# Sherline_Configuration.net
KiCad netlist of a schematic drawn in EAGLE
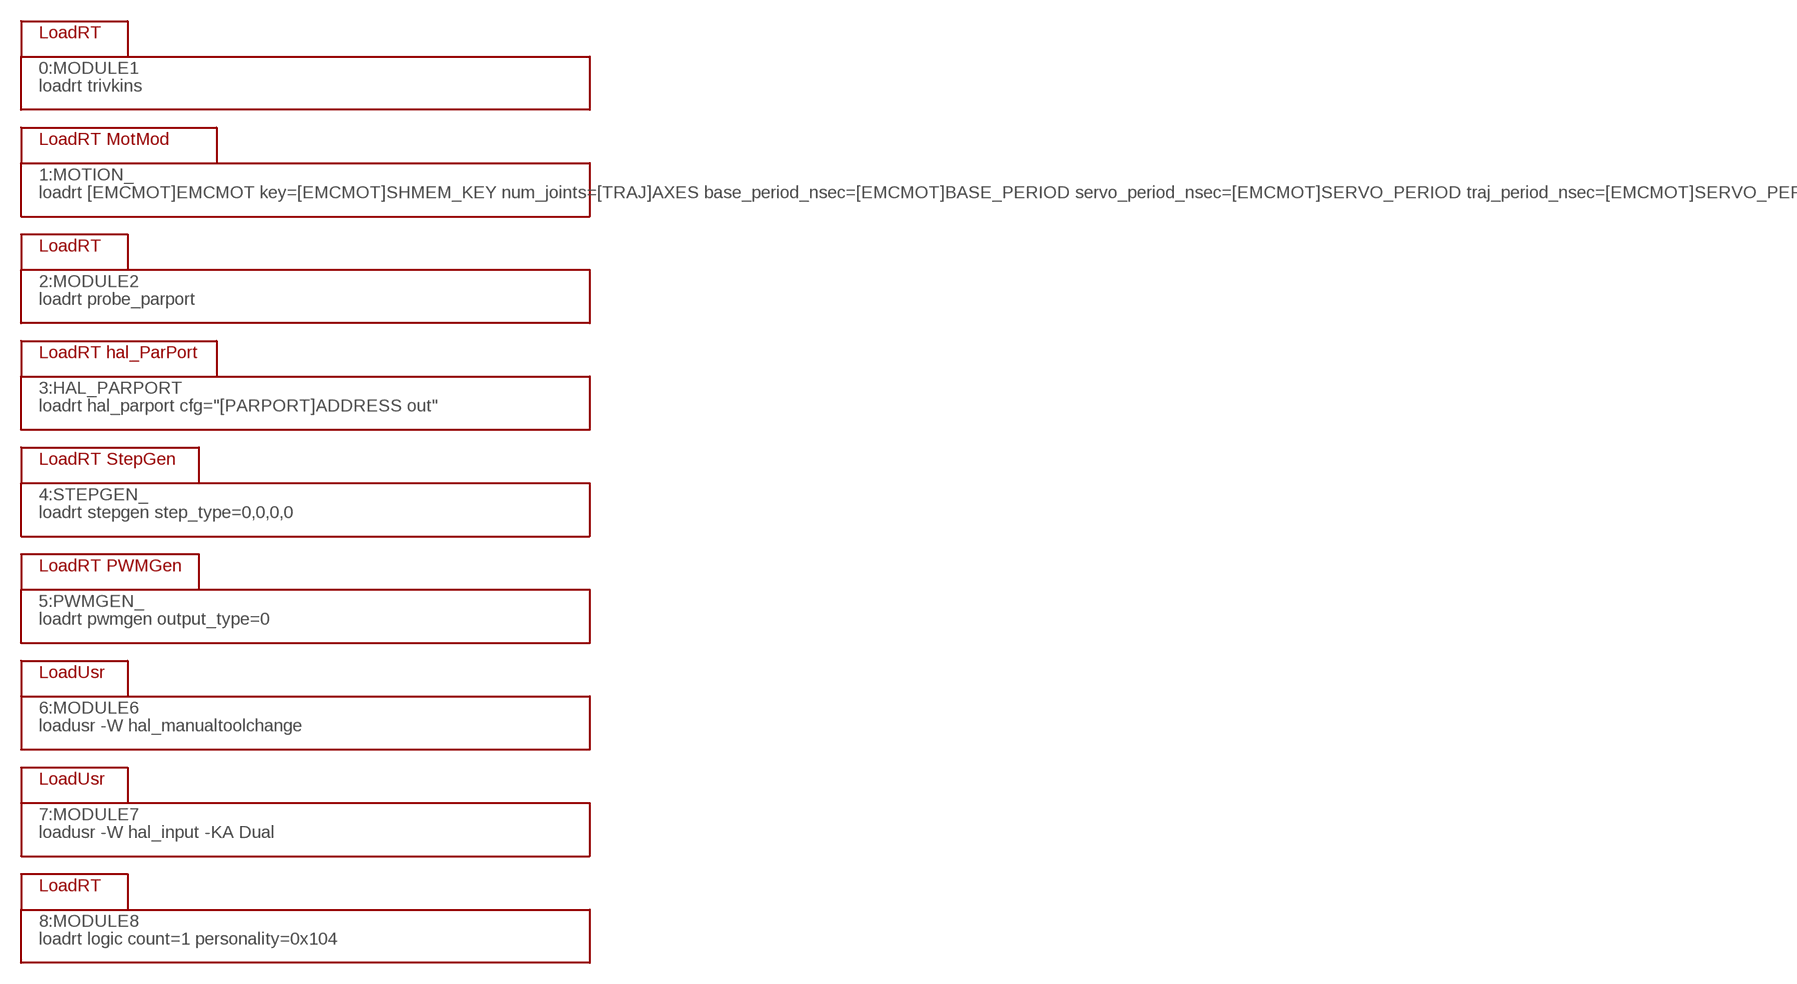
[diagram p0: schematic, sheet 1]
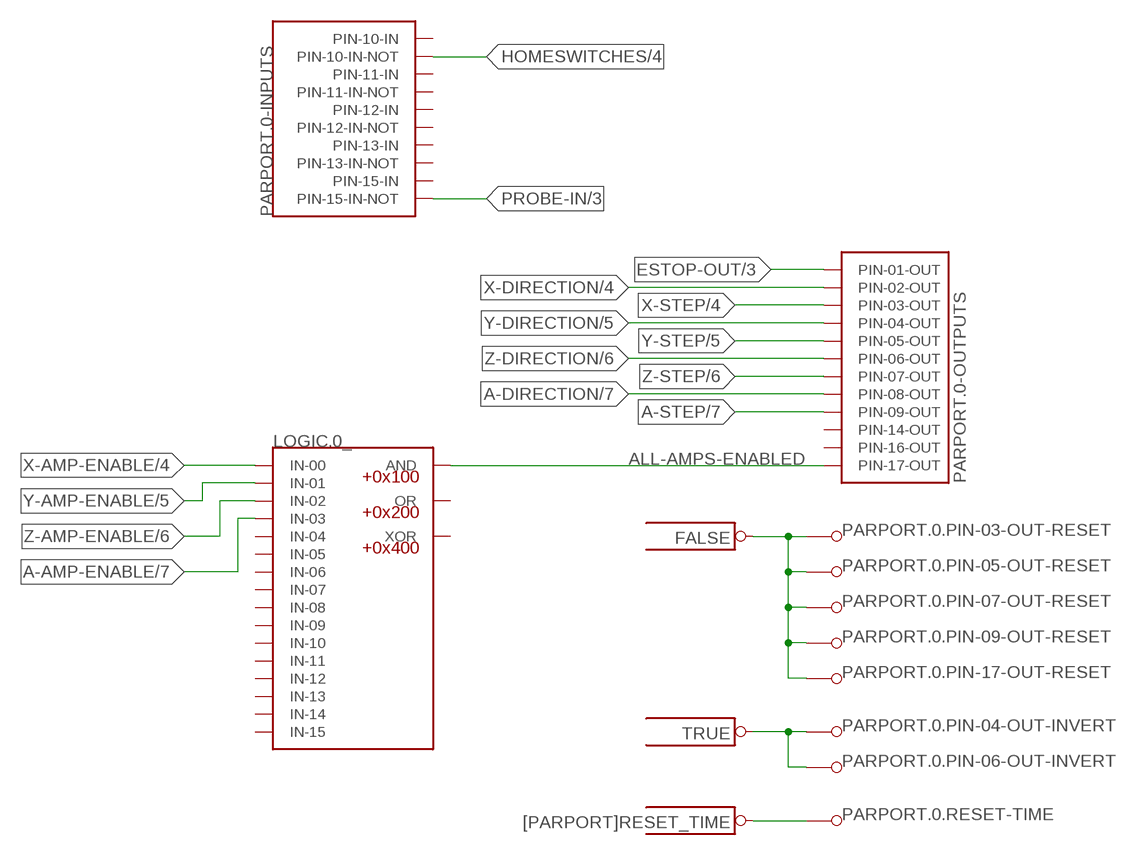
[diagram p1: schematic, sheet 2]
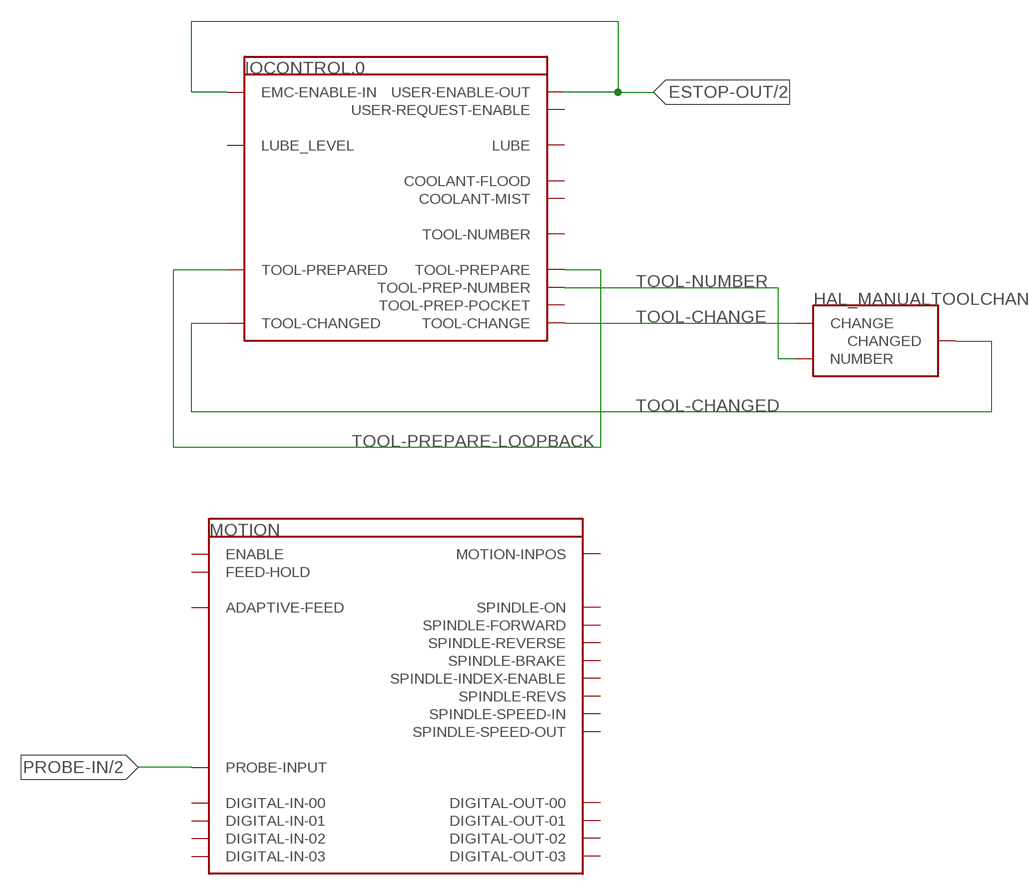
[diagram p2: schematic, sheet 3]
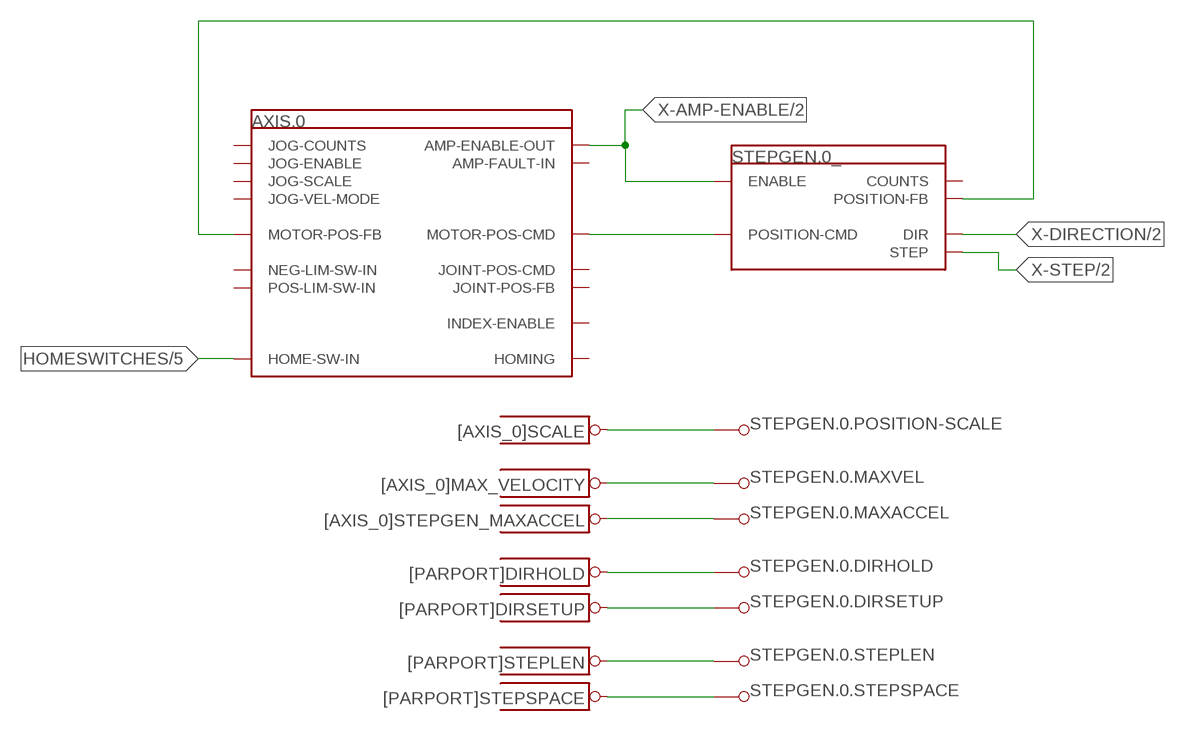
[diagram p3: schematic, sheet 4]
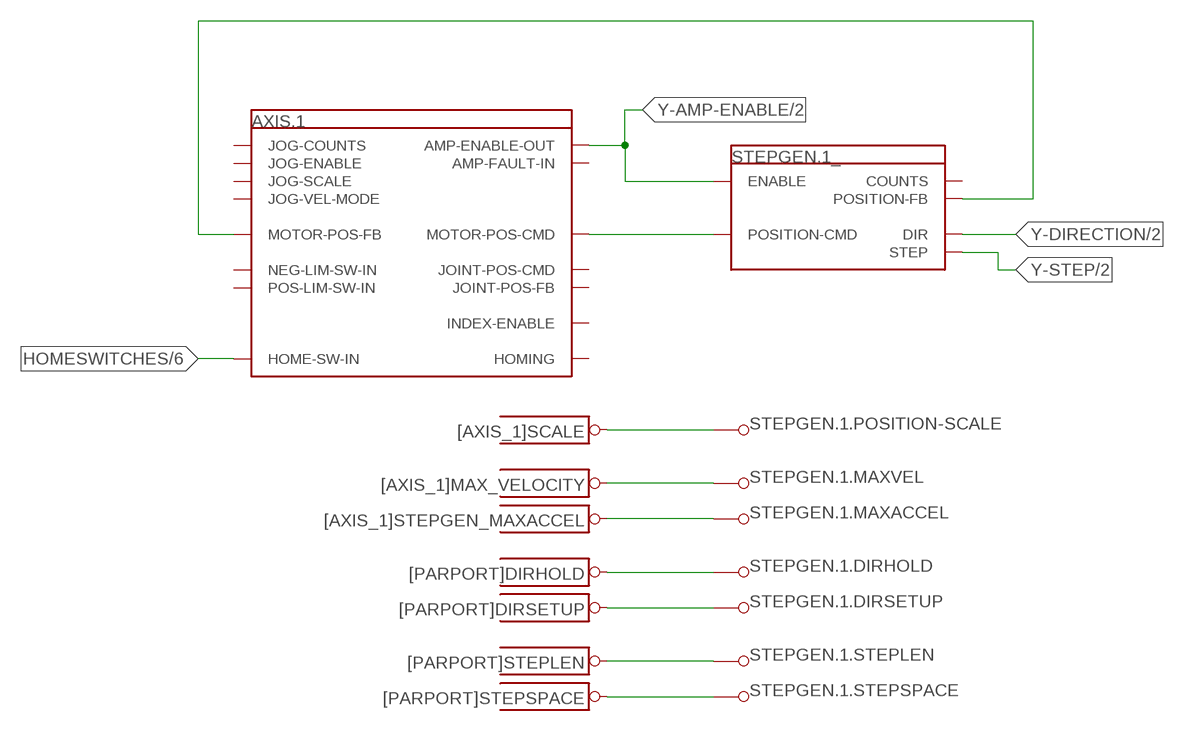
[diagram p4: schematic, sheet 5]
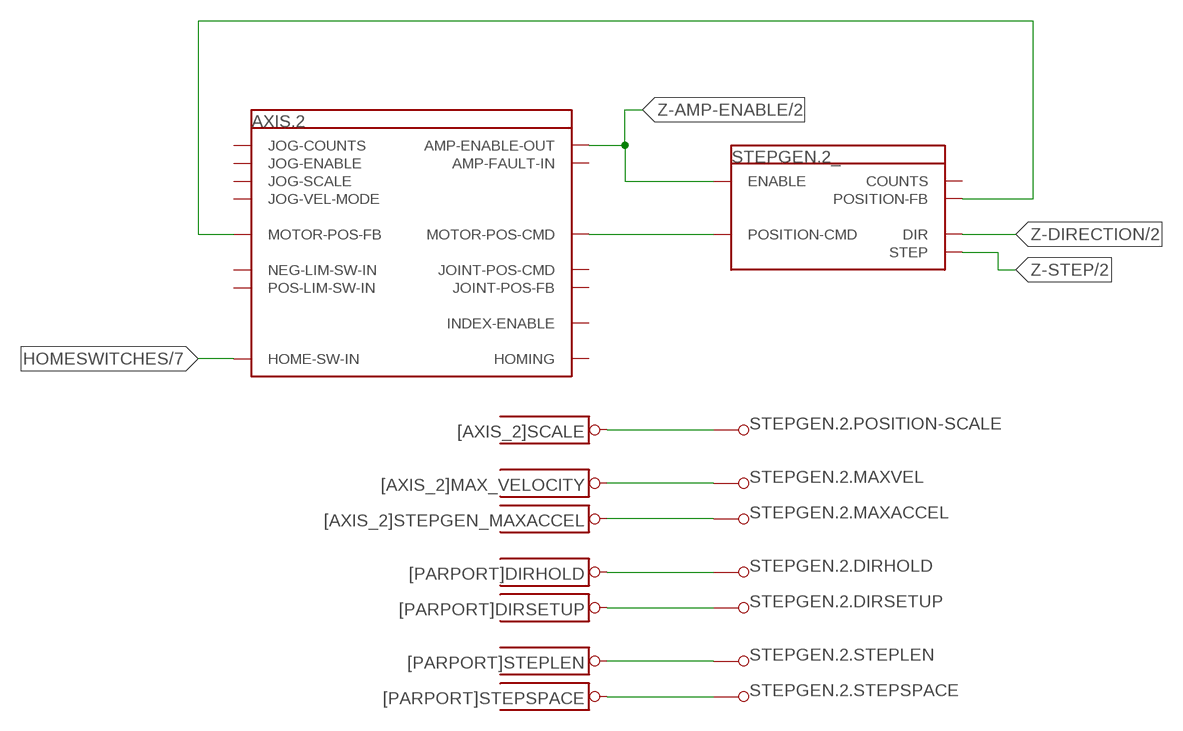
[diagram p5: schematic, sheet 6]
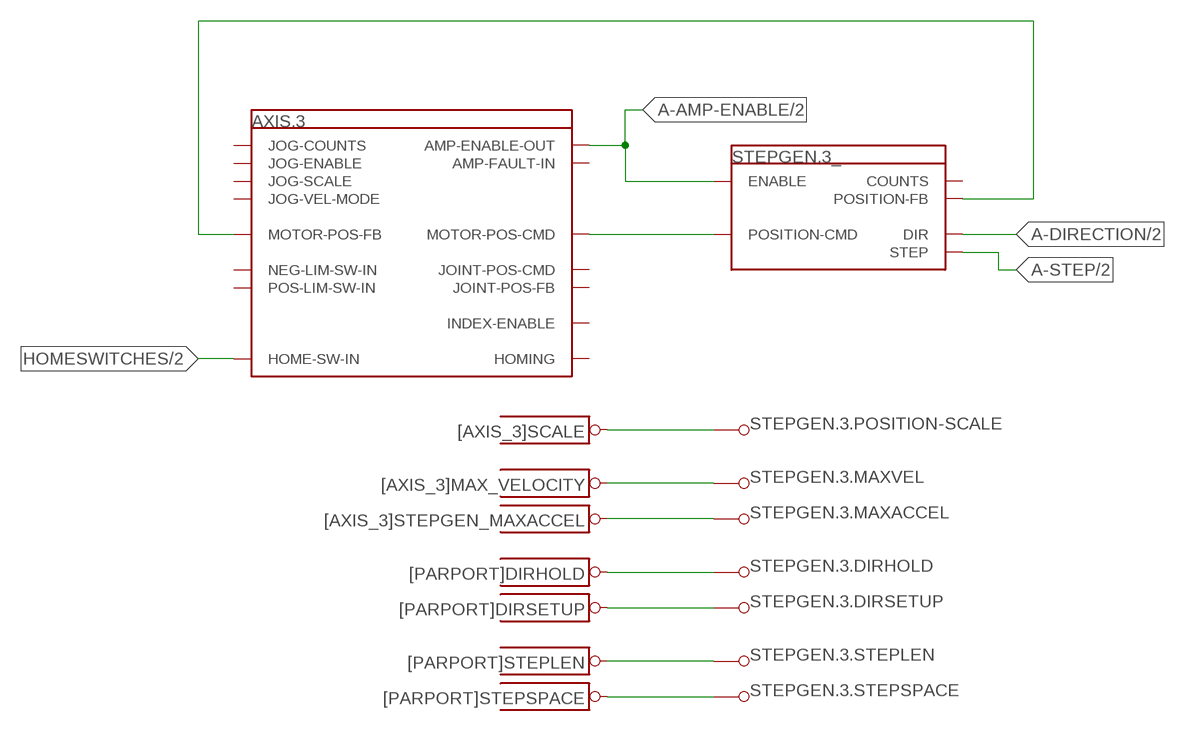
[diagram p6: schematic, sheet 7]
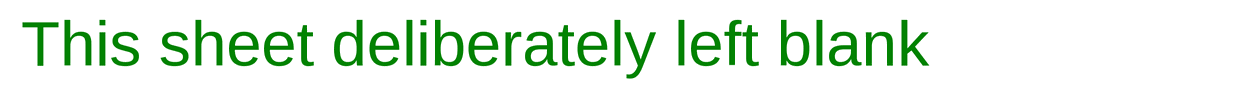
[diagram p7: schematic, sheet 8]
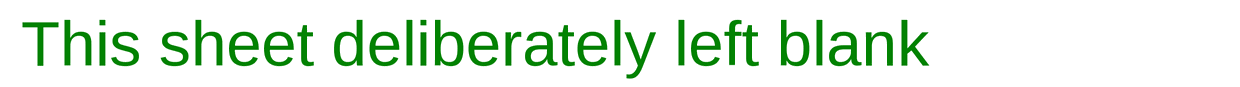
[diagram p8: schematic, sheet 9]
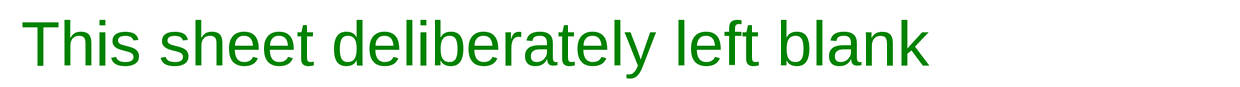
[diagram p9: schematic, sheet 10]
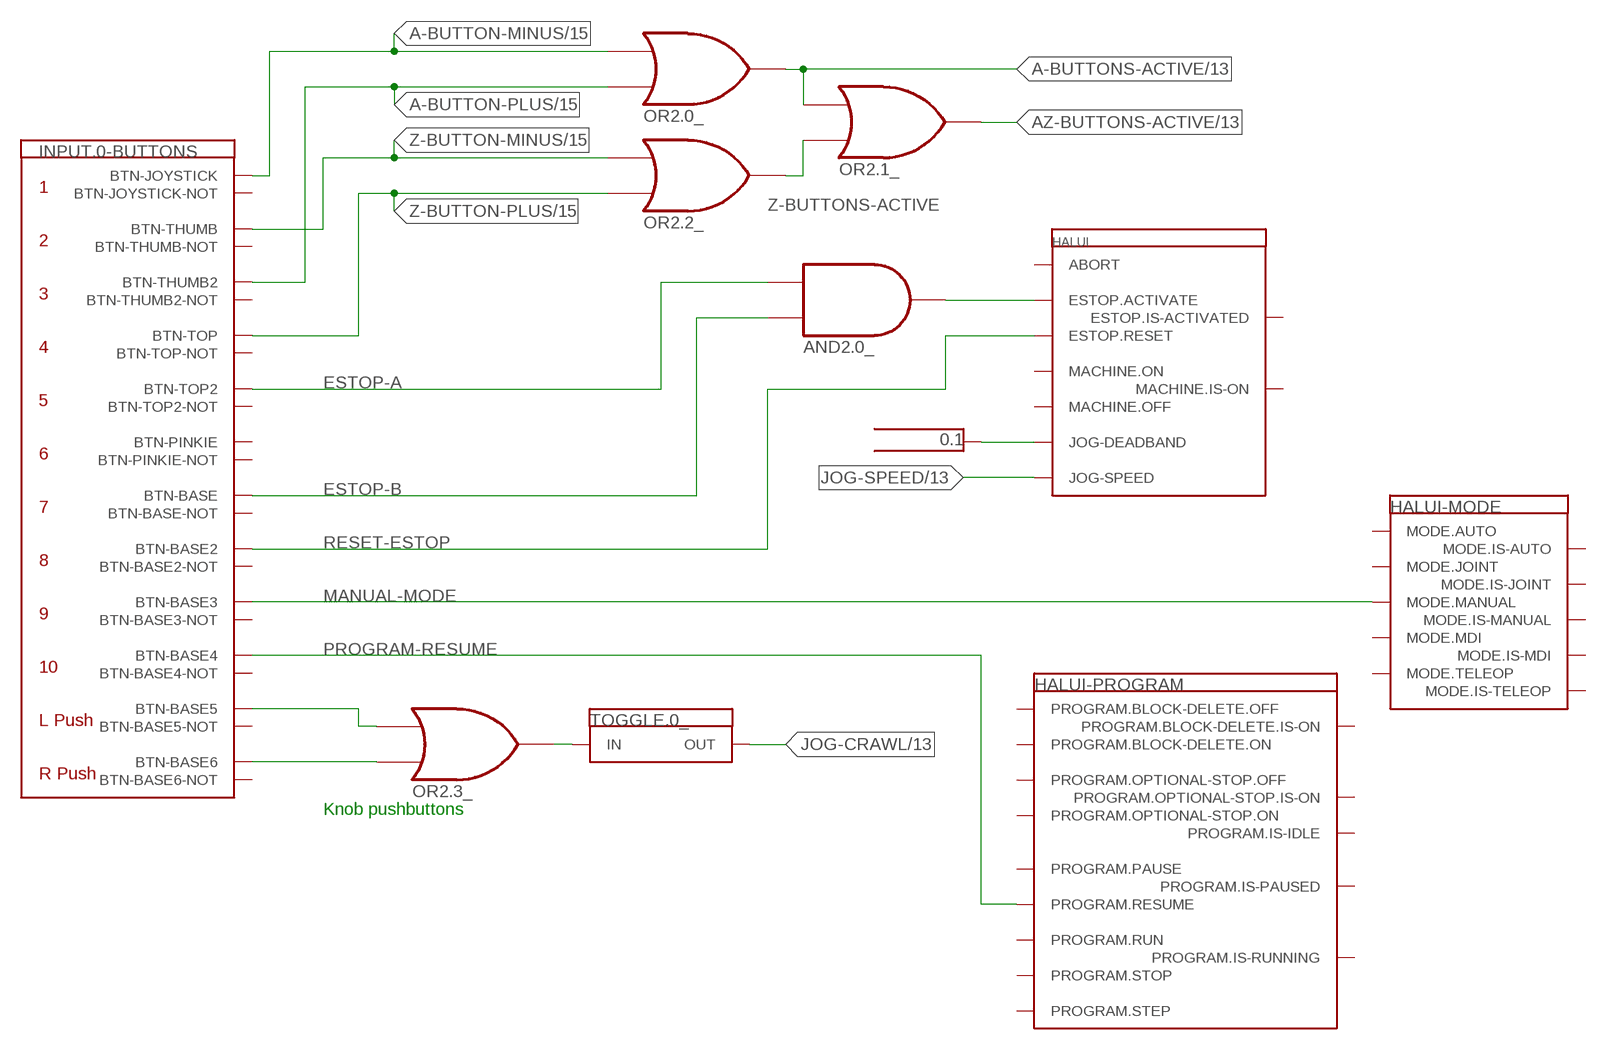
[diagram p10: schematic, sheet 11]
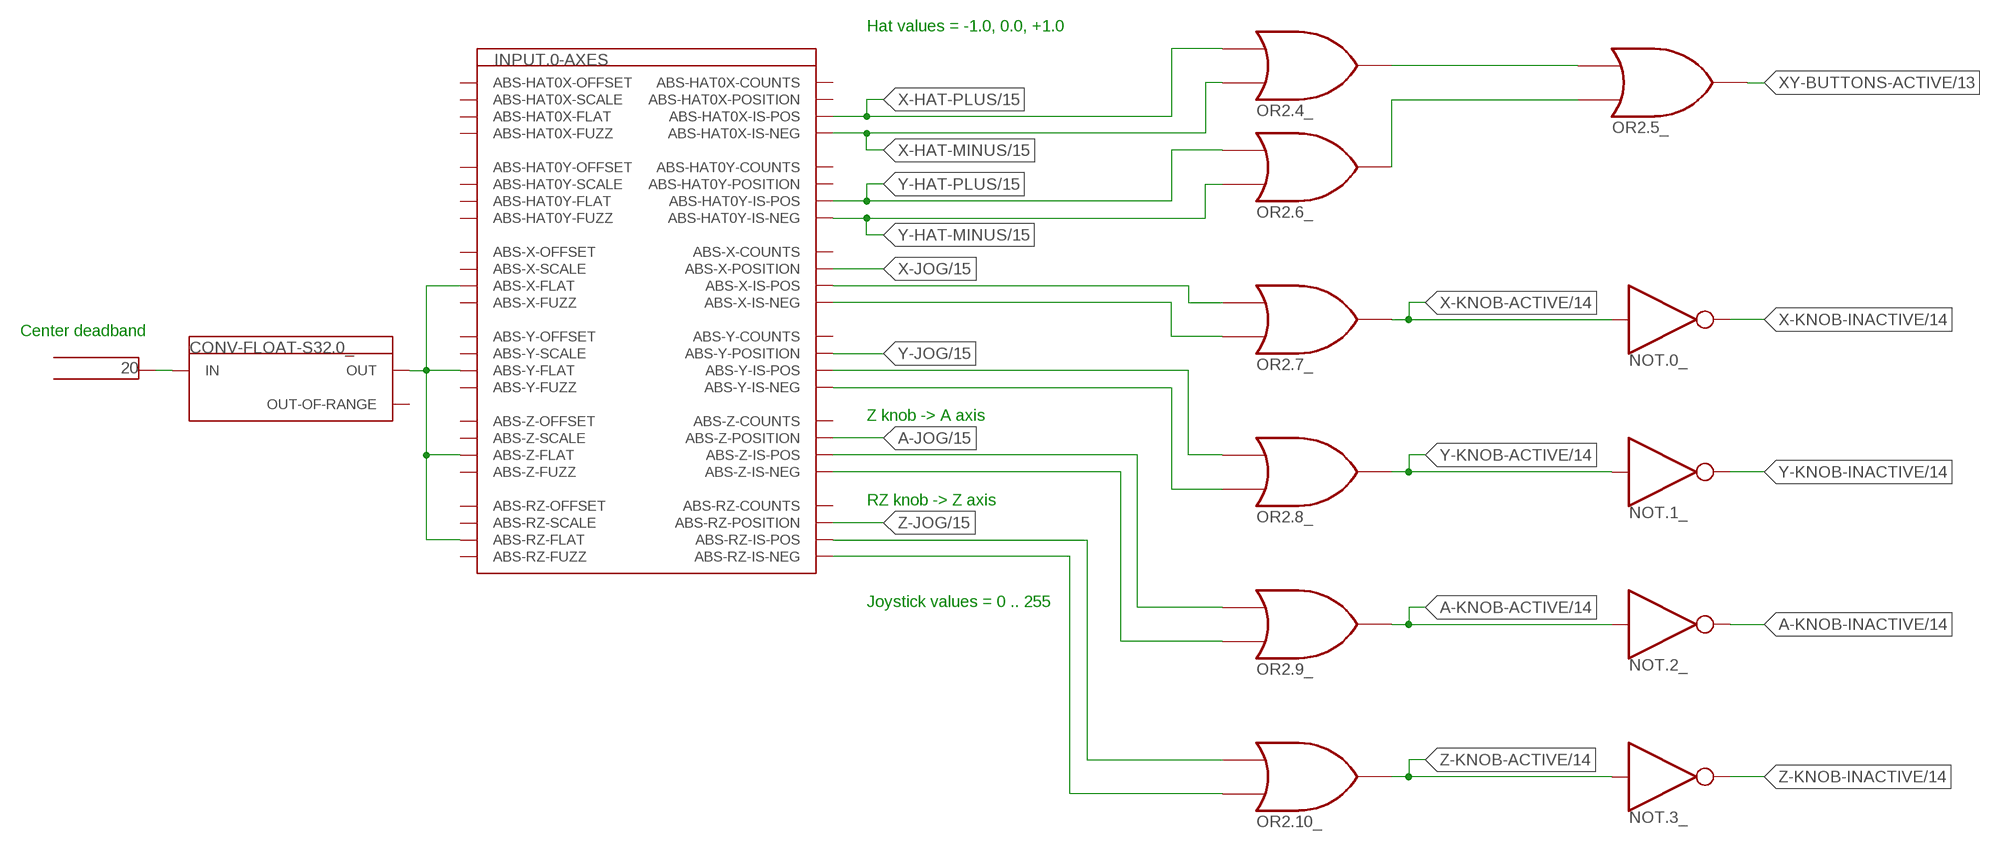
[diagram p11: schematic, sheet 12]
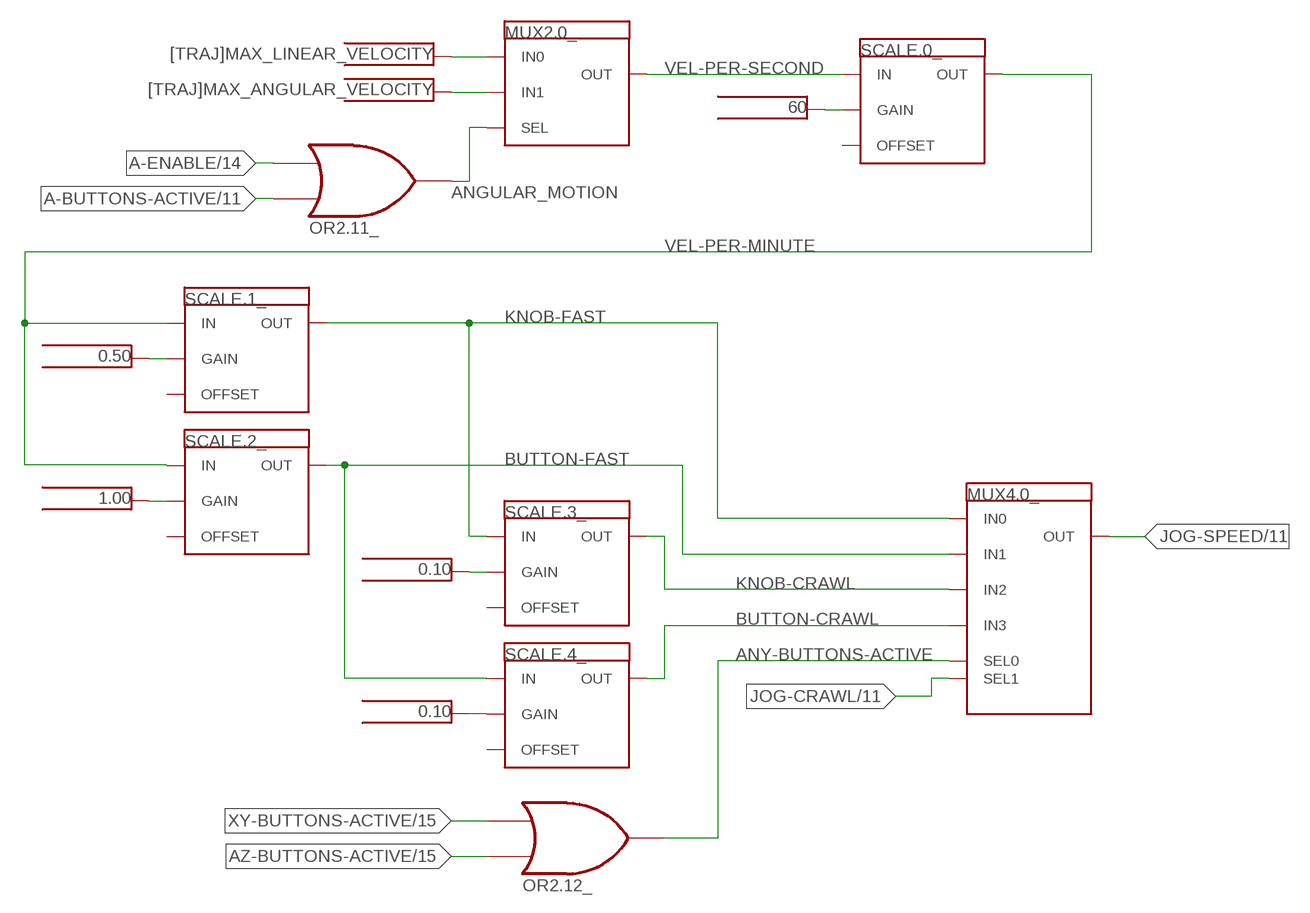
[diagram p12: schematic, sheet 13]
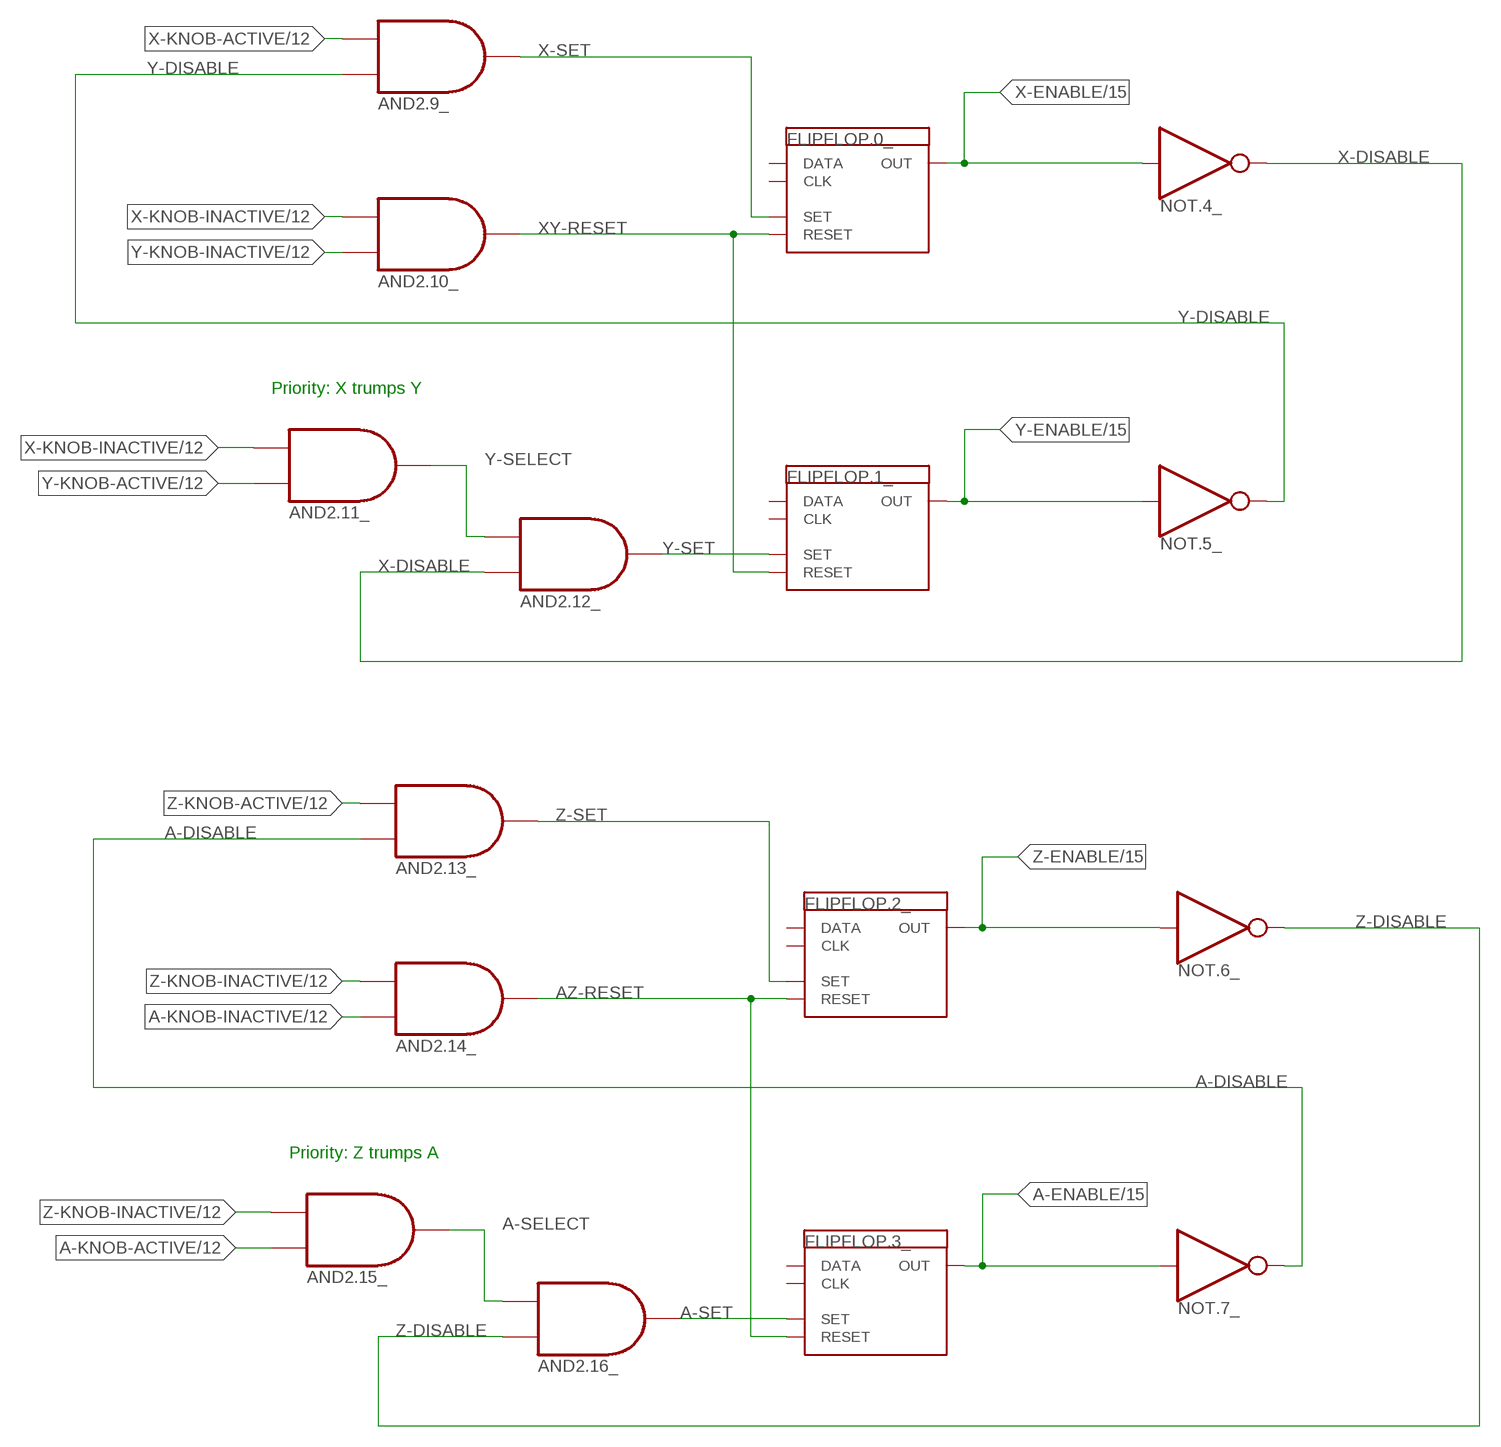
[diagram p13: schematic, sheet 14]
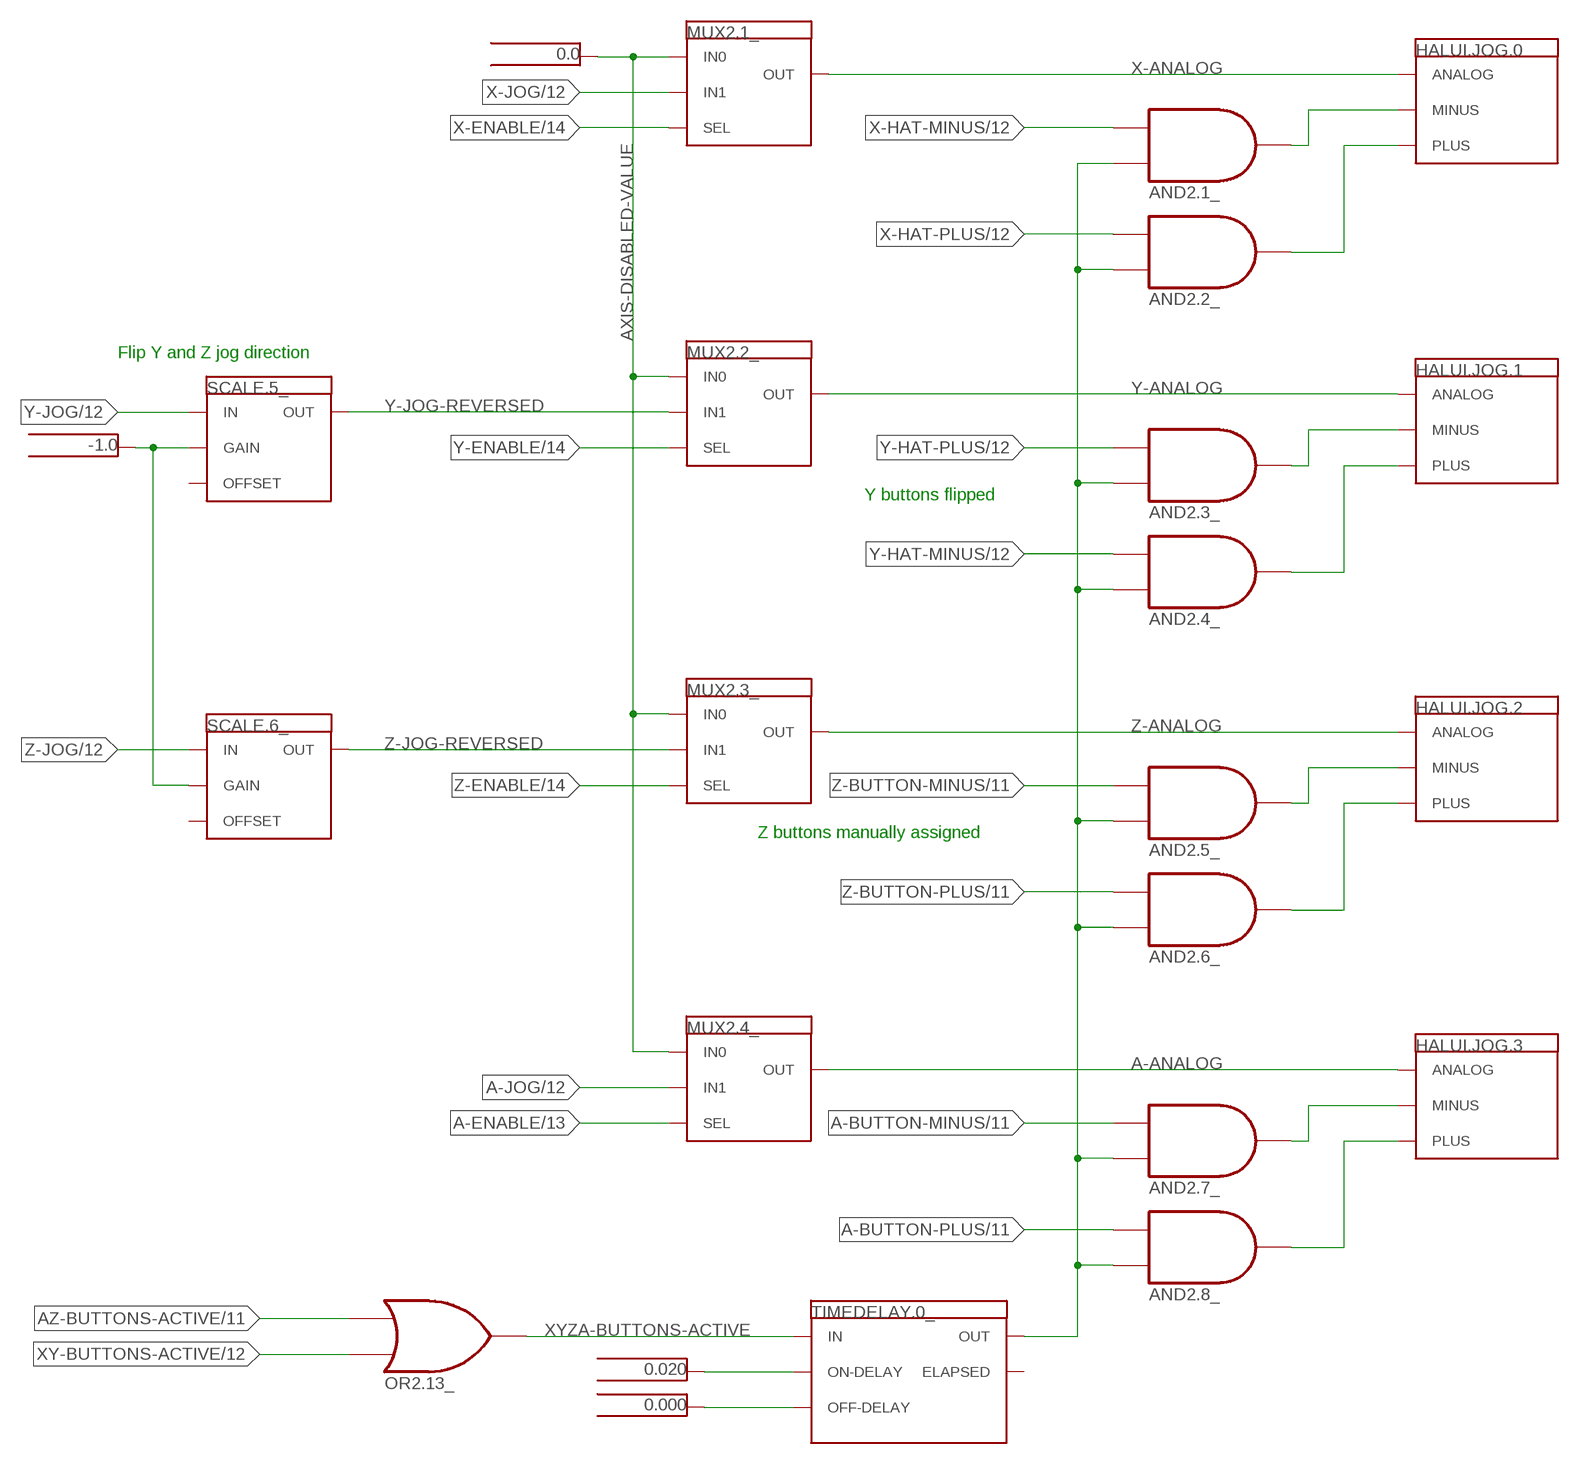
[diagram p14: schematic, sheet 15]
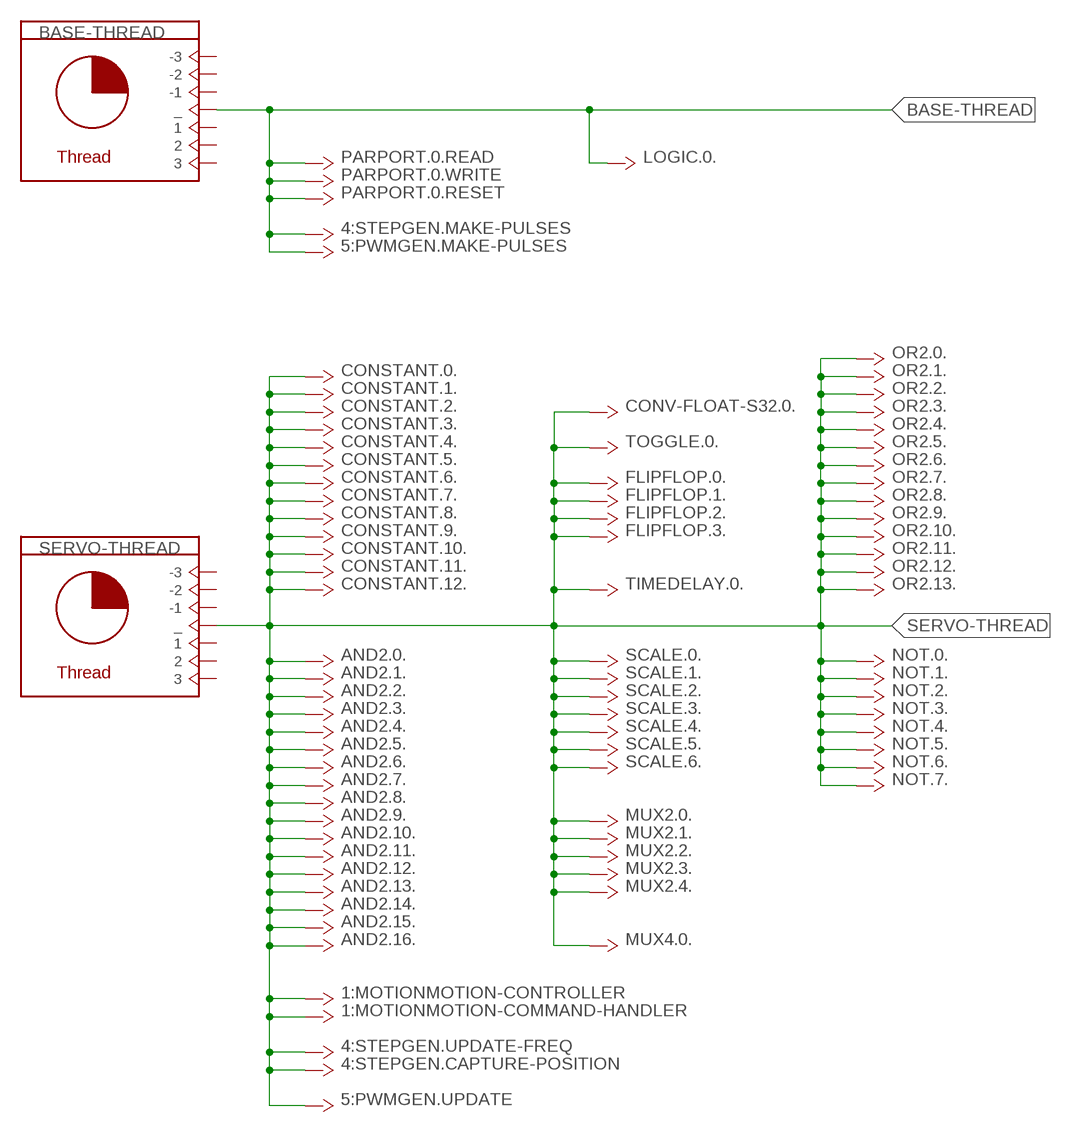
[diagram p15: schematic, sheet 16]

(export (version "E")
  (design (tool "Eeschema 10.0.6"))
  (components
    (comp (ref "1:MOTION")
      (value "loadrt [EMCMOT]EMCMOT key=[EMCMOT]SHMEM_KEY num_joints=[TRAJ]AXES base_period_nsec=[EMCMOT]BASE_PERIOD servo_period_nsec=[EMCMOT]SERVO_PERIOD traj_period_nsec=[EMCMOT]SERVO_PERIOD")
      (footprint "eagle-import:DUMMY")
      (libsource (lib "eagle-import") (part "LOADRT_MOTMOD"))
    )
    (comp (ref "4:STEPGEN")
      (value "loadrt stepgen step_type=0,0,0,0")
      (footprint "eagle-import:DUMMY")
      (libsource (lib "eagle-import") (part "LOADRT_STEPGEN"))
    )
    (comp (ref "5:PWMGEN")
      (value "loadrt pwmgen output_type=0")
      (footprint "eagle-import:DUMMY")
      (libsource (lib "eagle-import") (part "LOADRT_PWMGEN"))
    )
    (comp (ref "AND2.0")
      (value "AND2")
      (footprint "eagle-import:DUMMY")
      (libsource (lib "eagle-import") (part "AND2"))
    )
    (comp (ref "AND2.1")
      (value "AND2")
      (footprint "eagle-import:DUMMY")
      (libsource (lib "eagle-import") (part "AND2"))
    )
    (comp (ref "AND2.2")
      (value "AND2")
      (footprint "eagle-import:DUMMY")
      (libsource (lib "eagle-import") (part "AND2"))
    )
    (comp (ref "AND2.3")
      (value "AND2")
      (footprint "eagle-import:DUMMY")
      (libsource (lib "eagle-import") (part "AND2"))
    )
    (comp (ref "AND2.4")
      (value "AND2")
      (footprint "eagle-import:DUMMY")
      (libsource (lib "eagle-import") (part "AND2"))
    )
    (comp (ref "AND2.5")
      (value "AND2")
      (footprint "eagle-import:DUMMY")
      (libsource (lib "eagle-import") (part "AND2"))
    )
    (comp (ref "AND2.6")
      (value "AND2")
      (footprint "eagle-import:DUMMY")
      (libsource (lib "eagle-import") (part "AND2"))
    )
    (comp (ref "AND2.7")
      (value "AND2")
      (footprint "eagle-import:DUMMY")
      (libsource (lib "eagle-import") (part "AND2"))
    )
    (comp (ref "AND2.8")
      (value "AND2")
      (footprint "eagle-import:DUMMY")
      (libsource (lib "eagle-import") (part "AND2"))
    )
    (comp (ref "AND2.9")
      (value "AND2")
      (footprint "eagle-import:DUMMY")
      (libsource (lib "eagle-import") (part "AND2"))
    )
    (comp (ref "AND2.10")
      (value "AND2")
      (footprint "eagle-import:DUMMY")
      (libsource (lib "eagle-import") (part "AND2"))
    )
    (comp (ref "AND2.11")
      (value "AND2")
      (footprint "eagle-import:DUMMY")
      (libsource (lib "eagle-import") (part "AND2"))
    )
    (comp (ref "AND2.12")
      (value "AND2")
      (footprint "eagle-import:DUMMY")
      (libsource (lib "eagle-import") (part "AND2"))
    )
    (comp (ref "AND2.13")
      (value "AND2")
      (footprint "eagle-import:DUMMY")
      (libsource (lib "eagle-import") (part "AND2"))
    )
    (comp (ref "AND2.14")
      (value "AND2")
      (footprint "eagle-import:DUMMY")
      (libsource (lib "eagle-import") (part "AND2"))
    )
    (comp (ref "AND2.15")
      (value "AND2")
      (footprint "eagle-import:DUMMY")
      (libsource (lib "eagle-import") (part "AND2"))
    )
    (comp (ref "AND2.16")
      (value "AND2")
      (footprint "eagle-import:DUMMY")
      (libsource (lib "eagle-import") (part "AND2"))
    )
    (comp (ref "BASE-THREAD")
      (value "THREAD")
      (footprint "eagle-import:DUMMY")
      (libsource (lib "eagle-import") (part "THREAD"))
    )
    (comp (ref "CONSTANT.0")
      (value "0.1")
      (footprint "eagle-import:DUMMY")
      (libsource (lib "eagle-import") (part "CONSTANT"))
    )
    (comp (ref "CONSTANT.1")
      (value "20")
      (footprint "eagle-import:DUMMY")
      (libsource (lib "eagle-import") (part "CONSTANT"))
    )
    (comp (ref "CONSTANT.2")
      (value "[TRAJ]MAX_LINEAR_VELOCITY")
      (footprint "eagle-import:DUMMY")
      (libsource (lib "eagle-import") (part "CONSTANT"))
    )
    (comp (ref "CONSTANT.3")
      (value "[TRAJ]MAX_ANGULAR_VELOCITY")
      (footprint "eagle-import:DUMMY")
      (libsource (lib "eagle-import") (part "CONSTANT"))
    )
    (comp (ref "CONSTANT.4")
      (value "60")
      (footprint "eagle-import:DUMMY")
      (libsource (lib "eagle-import") (part "CONSTANT"))
    )
    (comp (ref "CONSTANT.5")
      (value "0.50")
      (footprint "eagle-import:DUMMY")
      (libsource (lib "eagle-import") (part "CONSTANT"))
    )
    (comp (ref "CONSTANT.6")
      (value "1.00")
      (footprint "eagle-import:DUMMY")
      (libsource (lib "eagle-import") (part "CONSTANT"))
    )
    (comp (ref "CONSTANT.7")
      (value "0.10")
      (footprint "eagle-import:DUMMY")
      (libsource (lib "eagle-import") (part "CONSTANT"))
    )
    (comp (ref "CONSTANT.8")
      (value "0.10")
      (footprint "eagle-import:DUMMY")
      (libsource (lib "eagle-import") (part "CONSTANT"))
    )
    (comp (ref "CONSTANT.9")
      (value "0.0")
      (footprint "eagle-import:DUMMY")
      (libsource (lib "eagle-import") (part "CONSTANT"))
    )
    (comp (ref "CONSTANT.10")
      (value "-1.0")
      (footprint "eagle-import:DUMMY")
      (libsource (lib "eagle-import") (part "CONSTANT"))
    )
    (comp (ref "CONSTANT.11")
      (value "0.020")
      (footprint "eagle-import:DUMMY")
      (libsource (lib "eagle-import") (part "CONSTANT"))
    )
    (comp (ref "CONSTANT.12")
      (value "0.000")
      (footprint "eagle-import:DUMMY")
      (libsource (lib "eagle-import") (part "CONSTANT"))
    )
    (comp (ref "CONV-FLOAT-S32.0")
      (value "CONV_FLOAT_S32")
      (footprint "eagle-import:DUMMY")
      (libsource (lib "eagle-import") (part "CONV_FLOAT_S32"))
    )
    (comp (ref "FLIPFLOP.0")
      (value "FLIPFLOP")
      (footprint "eagle-import:DUMMY")
      (libsource (lib "eagle-import") (part "FLIPFLOP"))
    )
    (comp (ref "FLIPFLOP.1")
      (value "FLIPFLOP")
      (footprint "eagle-import:DUMMY")
      (libsource (lib "eagle-import") (part "FLIPFLOP"))
    )
    (comp (ref "FLIPFLOP.2")
      (value "FLIPFLOP")
      (footprint "eagle-import:DUMMY")
      (libsource (lib "eagle-import") (part "FLIPFLOP"))
    )
    (comp (ref "FLIPFLOP.3")
      (value "FLIPFLOP")
      (footprint "eagle-import:DUMMY")
      (libsource (lib "eagle-import") (part "FLIPFLOP"))
    )
    (comp (ref "LOGIC.0")
      (value "LOGIC")
      (footprint "eagle-import:DUMMY")
      (libsource (lib "eagle-import") (part "LOGIC"))
    )
    (comp (ref "MUX2.0")
      (value "MUX2")
      (footprint "eagle-import:DUMMY")
      (libsource (lib "eagle-import") (part "MUX2"))
    )
    (comp (ref "MUX2.1")
      (value "MUX2")
      (footprint "eagle-import:DUMMY")
      (libsource (lib "eagle-import") (part "MUX2"))
    )
    (comp (ref "MUX2.2")
      (value "MUX2")
      (footprint "eagle-import:DUMMY")
      (libsource (lib "eagle-import") (part "MUX2"))
    )
    (comp (ref "MUX2.3")
      (value "MUX2")
      (footprint "eagle-import:DUMMY")
      (libsource (lib "eagle-import") (part "MUX2"))
    )
    (comp (ref "MUX2.4")
      (value "MUX2")
      (footprint "eagle-import:DUMMY")
      (libsource (lib "eagle-import") (part "MUX2"))
    )
    (comp (ref "MUX4.0")
      (value "MUX4")
      (footprint "eagle-import:DUMMY")
      (libsource (lib "eagle-import") (part "MUX4"))
    )
    (comp (ref "NOT.0")
      (value "NOT")
      (footprint "eagle-import:DUMMY")
      (libsource (lib "eagle-import") (part "NOT"))
    )
    (comp (ref "NOT.1")
      (value "NOT")
      (footprint "eagle-import:DUMMY")
      (libsource (lib "eagle-import") (part "NOT"))
    )
    (comp (ref "NOT.2")
      (value "NOT")
      (footprint "eagle-import:DUMMY")
      (libsource (lib "eagle-import") (part "NOT"))
    )
    (comp (ref "NOT.3")
      (value "NOT")
      (footprint "eagle-import:DUMMY")
      (libsource (lib "eagle-import") (part "NOT"))
    )
    (comp (ref "NOT.4")
      (value "NOT")
      (footprint "eagle-import:DUMMY")
      (libsource (lib "eagle-import") (part "NOT"))
    )
    (comp (ref "NOT.5")
      (value "NOT")
      (footprint "eagle-import:DUMMY")
      (libsource (lib "eagle-import") (part "NOT"))
    )
    (comp (ref "NOT.6")
      (value "NOT")
      (footprint "eagle-import:DUMMY")
      (libsource (lib "eagle-import") (part "NOT"))
    )
    (comp (ref "NOT.7")
      (value "NOT")
      (footprint "eagle-import:DUMMY")
      (libsource (lib "eagle-import") (part "NOT"))
    )
    (comp (ref "OR2.0")
      (value "OR2")
      (footprint "eagle-import:DUMMY")
      (libsource (lib "eagle-import") (part "OR2"))
    )
    (comp (ref "OR2.1")
      (value "OR2")
      (footprint "eagle-import:DUMMY")
      (libsource (lib "eagle-import") (part "OR2"))
    )
    (comp (ref "OR2.2")
      (value "OR2")
      (footprint "eagle-import:DUMMY")
      (libsource (lib "eagle-import") (part "OR2"))
    )
    (comp (ref "OR2.3")
      (value "OR2")
      (footprint "eagle-import:DUMMY")
      (libsource (lib "eagle-import") (part "OR2"))
    )
    (comp (ref "OR2.4")
      (value "OR2")
      (footprint "eagle-import:DUMMY")
      (libsource (lib "eagle-import") (part "OR2"))
    )
    (comp (ref "OR2.5")
      (value "OR2")
      (footprint "eagle-import:DUMMY")
      (libsource (lib "eagle-import") (part "OR2"))
    )
    (comp (ref "OR2.6")
      (value "OR2")
      (footprint "eagle-import:DUMMY")
      (libsource (lib "eagle-import") (part "OR2"))
    )
    (comp (ref "OR2.7")
      (value "OR2")
      (footprint "eagle-import:DUMMY")
      (libsource (lib "eagle-import") (part "OR2"))
    )
    (comp (ref "OR2.8")
      (value "OR2")
      (footprint "eagle-import:DUMMY")
      (libsource (lib "eagle-import") (part "OR2"))
    )
    (comp (ref "OR2.9")
      (value "OR2")
      (footprint "eagle-import:DUMMY")
      (libsource (lib "eagle-import") (part "OR2"))
    )
    (comp (ref "OR2.10")
      (value "OR2")
      (footprint "eagle-import:DUMMY")
      (libsource (lib "eagle-import") (part "OR2"))
    )
    (comp (ref "OR2.11")
      (value "OR2")
      (footprint "eagle-import:DUMMY")
      (libsource (lib "eagle-import") (part "OR2"))
    )
    (comp (ref "OR2.12")
      (value "OR2")
      (footprint "eagle-import:DUMMY")
      (libsource (lib "eagle-import") (part "OR2"))
    )
    (comp (ref "OR2.13")
      (value "OR2")
      (footprint "eagle-import:DUMMY")
      (libsource (lib "eagle-import") (part "OR2"))
    )
    (comp (ref "PARPORT.0")
      (value "PARPORT-OUT")
      (footprint "eagle-import:DUMMY")
      (libsource (lib "eagle-import") (part "PARPORT-OUT"))
    )
    (comp (ref "SCALE.0")
      (value "SCALE")
      (footprint "eagle-import:DUMMY")
      (libsource (lib "eagle-import") (part "SCALE"))
    )
    (comp (ref "SCALE.1")
      (value "SCALE")
      (footprint "eagle-import:DUMMY")
      (libsource (lib "eagle-import") (part "SCALE"))
    )
    (comp (ref "SCALE.2")
      (value "SCALE")
      (footprint "eagle-import:DUMMY")
      (libsource (lib "eagle-import") (part "SCALE"))
    )
    (comp (ref "SCALE.3")
      (value "SCALE")
      (footprint "eagle-import:DUMMY")
      (libsource (lib "eagle-import") (part "SCALE"))
    )
    (comp (ref "SCALE.4")
      (value "SCALE")
      (footprint "eagle-import:DUMMY")
      (libsource (lib "eagle-import") (part "SCALE"))
    )
    (comp (ref "SCALE.5")
      (value "SCALE")
      (footprint "eagle-import:DUMMY")
      (libsource (lib "eagle-import") (part "SCALE"))
    )
    (comp (ref "SCALE.6")
      (value "SCALE")
      (footprint "eagle-import:DUMMY")
      (libsource (lib "eagle-import") (part "SCALE"))
    )
    (comp (ref "SERVO-THREAD")
      (value "THREAD")
      (footprint "eagle-import:DUMMY")
      (libsource (lib "eagle-import") (part "THREAD"))
    )
    (comp (ref "TIMEDELAY.0")
      (value "TIMEDELAY")
      (footprint "eagle-import:DUMMY")
      (libsource (lib "eagle-import") (part "TIMEDELAY"))
    )
    (comp (ref "TOGGLE.0")
      (value "TOGGLE")
      (footprint "eagle-import:DUMMY")
      (libsource (lib "eagle-import") (part "TOGGLE"))
    )
    (comp (ref "AXIS.3")
      (value "AXIS")
      (footprint "eagle-import:DUMMY")
      (libsource (lib "eagle-import") (part "AXIS"))
    )
    (comp (ref "PARAMETER23")
      (value "[AXIS_3]MAX_VELOCITY")
      (footprint "eagle-import:DUMMY")
      (libsource (lib "eagle-import") (part "PARAMETER"))
    )
    (comp (ref "PARAMETER24")
      (value "[AXIS_3]STEPGEN_MAXACCEL")
      (footprint "eagle-import:DUMMY")
      (libsource (lib "eagle-import") (part "PARAMETER"))
    )
    (comp (ref "PARAMETER25")
      (value "[PARPORT]DIRHOLD")
      (footprint "eagle-import:DUMMY")
      (libsource (lib "eagle-import") (part "PARAMETER"))
    )
    (comp (ref "PARAMETER26")
      (value "[PARPORT]DIRSETUP")
      (footprint "eagle-import:DUMMY")
      (libsource (lib "eagle-import") (part "PARAMETER"))
    )
    (comp (ref "PARAMETER27")
      (value "[PARPORT]STEPLEN")
      (footprint "eagle-import:DUMMY")
      (libsource (lib "eagle-import") (part "PARAMETER"))
    )
    (comp (ref "PARAMETER28")
      (value "[PARPORT]STEPSPACE")
      (footprint "eagle-import:DUMMY")
      (libsource (lib "eagle-import") (part "PARAMETER"))
    )
    (comp (ref "PARAMETER29")
      (value "[AXIS_3]SCALE")
      (footprint "eagle-import:DUMMY")
      (libsource (lib "eagle-import") (part "PARAMETER"))
    )
    (comp (ref "STEPGEN.3")
      (value "STEPGEN-0")
      (footprint "eagle-import:DUMMY")
      (libsource (lib "eagle-import") (part "STEPGEN-0"))
    )
    (comp (ref "AXIS.1")
      (value "AXIS")
      (footprint "eagle-import:DUMMY")
      (libsource (lib "eagle-import") (part "AXIS"))
    )
    (comp (ref "PARAMETER9")
      (value "[AXIS_1]MAX_VELOCITY")
      (footprint "eagle-import:DUMMY")
      (libsource (lib "eagle-import") (part "PARAMETER"))
    )
    (comp (ref "PARAMETER10")
      (value "[AXIS_1]STEPGEN_MAXACCEL")
      (footprint "eagle-import:DUMMY")
      (libsource (lib "eagle-import") (part "PARAMETER"))
    )
    (comp (ref "PARAMETER11")
      (value "[PARPORT]DIRHOLD")
      (footprint "eagle-import:DUMMY")
      (libsource (lib "eagle-import") (part "PARAMETER"))
    )
    (comp (ref "PARAMETER12")
      (value "[PARPORT]DIRSETUP")
      (footprint "eagle-import:DUMMY")
      (libsource (lib "eagle-import") (part "PARAMETER"))
    )
    (comp (ref "PARAMETER13")
      (value "[PARPORT]STEPLEN")
      (footprint "eagle-import:DUMMY")
      (libsource (lib "eagle-import") (part "PARAMETER"))
    )
    (comp (ref "PARAMETER14")
      (value "[PARPORT]STEPSPACE")
      (footprint "eagle-import:DUMMY")
      (libsource (lib "eagle-import") (part "PARAMETER"))
    )
    (comp (ref "PARAMETER15")
      (value "[AXIS_1]SCALE")
      (footprint "eagle-import:DUMMY")
      (libsource (lib "eagle-import") (part "PARAMETER"))
    )
    (comp (ref "STEPGEN.1")
      (value "STEPGEN-0")
      (footprint "eagle-import:DUMMY")
      (libsource (lib "eagle-import") (part "STEPGEN-0"))
    )
    (comp (ref "HALUI")
      (value "HALUI")
      (footprint "eagle-import:DUMMY")
      (libsource (lib "eagle-import") (part "HALUI"))
    )
    (comp (ref "INPUT.0")
      (value "LOGITECH-DUAL-ACTION-GAMEPAD")
      (footprint "eagle-import:DUMMY")
      (libsource (lib "eagle-import") (part "LOGITECH-DUAL-ACTION-GAMEPAD"))
    )
    (comp (ref "0:MODULE1")
      (value "loadrt trivkins")
      (footprint "eagle-import:DUMMY")
      (libsource (lib "eagle-import") (part "LOADRT"))
    )
    (comp (ref "2:MODULE2")
      (value "loadrt probe_parport")
      (footprint "eagle-import:DUMMY")
      (libsource (lib "eagle-import") (part "LOADRT"))
    )
    (comp (ref "3:HAL_PARPORT")
      (value "loadrt hal_parport cfg=\"[PARPORT]ADDRESS out\"")
      (footprint "eagle-import:DUMMY")
      (libsource (lib "eagle-import") (part "LOADRT_PARPORT"))
    )
    (comp (ref "8:MODULE8")
      (value "loadrt logic count=1 personality=0x104")
      (footprint "eagle-import:DUMMY")
      (libsource (lib "eagle-import") (part "LOADRT"))
    )
    (comp (ref "PARAMETER0")
      (value "[PARPORT]RESET_TIME")
      (footprint "eagle-import:DUMMY")
      (libsource (lib "eagle-import") (part "PARAMETER"))
    )
    (comp (ref "PARAMETER8")
      (value "FALSE")
      (footprint "eagle-import:DUMMY")
      (libsource (lib "eagle-import") (part "PARAMETER"))
    )
    (comp (ref "PARAMETER30")
      (value "TRUE")
      (footprint "eagle-import:DUMMY")
      (libsource (lib "eagle-import") (part "PARAMETER"))
    )
    (comp (ref "AXIS.0")
      (value "AXIS")
      (footprint "eagle-import:DUMMY")
      (libsource (lib "eagle-import") (part "AXIS"))
    )
    (comp (ref "PARAMETER1")
      (value "[AXIS_0]MAX_VELOCITY")
      (footprint "eagle-import:DUMMY")
      (libsource (lib "eagle-import") (part "PARAMETER"))
    )
    (comp (ref "PARAMETER2")
      (value "[AXIS_0]STEPGEN_MAXACCEL")
      (footprint "eagle-import:DUMMY")
      (libsource (lib "eagle-import") (part "PARAMETER"))
    )
    (comp (ref "PARAMETER3")
      (value "[PARPORT]DIRHOLD")
      (footprint "eagle-import:DUMMY")
      (libsource (lib "eagle-import") (part "PARAMETER"))
    )
    (comp (ref "PARAMETER4")
      (value "[PARPORT]DIRSETUP")
      (footprint "eagle-import:DUMMY")
      (libsource (lib "eagle-import") (part "PARAMETER"))
    )
    (comp (ref "PARAMETER5")
      (value "[PARPORT]STEPLEN")
      (footprint "eagle-import:DUMMY")
      (libsource (lib "eagle-import") (part "PARAMETER"))
    )
    (comp (ref "PARAMETER6")
      (value "[PARPORT]STEPSPACE")
      (footprint "eagle-import:DUMMY")
      (libsource (lib "eagle-import") (part "PARAMETER"))
    )
    (comp (ref "PARAMETER7")
      (value "[AXIS_0]SCALE")
      (footprint "eagle-import:DUMMY")
      (libsource (lib "eagle-import") (part "PARAMETER"))
    )
    (comp (ref "STEPGEN.0")
      (value "STEPGEN-0")
      (footprint "eagle-import:DUMMY")
      (libsource (lib "eagle-import") (part "STEPGEN-0"))
    )
    (comp (ref "AXIS.2")
      (value "AXIS")
      (footprint "eagle-import:DUMMY")
      (libsource (lib "eagle-import") (part "AXIS"))
    )
    (comp (ref "PARAMETER16")
      (value "[AXIS_2]MAX_VELOCITY")
      (footprint "eagle-import:DUMMY")
      (libsource (lib "eagle-import") (part "PARAMETER"))
    )
    (comp (ref "PARAMETER17")
      (value "[AXIS_2]STEPGEN_MAXACCEL")
      (footprint "eagle-import:DUMMY")
      (libsource (lib "eagle-import") (part "PARAMETER"))
    )
    (comp (ref "PARAMETER18")
      (value "[PARPORT]DIRHOLD")
      (footprint "eagle-import:DUMMY")
      (libsource (lib "eagle-import") (part "PARAMETER"))
    )
    (comp (ref "PARAMETER19")
      (value "[PARPORT]DIRSETUP")
      (footprint "eagle-import:DUMMY")
      (libsource (lib "eagle-import") (part "PARAMETER"))
    )
    (comp (ref "PARAMETER20")
      (value "[PARPORT]STEPLEN")
      (footprint "eagle-import:DUMMY")
      (libsource (lib "eagle-import") (part "PARAMETER"))
    )
    (comp (ref "PARAMETER21")
      (value "[PARPORT]STEPSPACE")
      (footprint "eagle-import:DUMMY")
      (libsource (lib "eagle-import") (part "PARAMETER"))
    )
    (comp (ref "PARAMETER22")
      (value "[AXIS_2]SCALE")
      (footprint "eagle-import:DUMMY")
      (libsource (lib "eagle-import") (part "PARAMETER"))
    )
    (comp (ref "STEPGEN.2")
      (value "STEPGEN-0")
      (footprint "eagle-import:DUMMY")
      (libsource (lib "eagle-import") (part "STEPGEN-0"))
    )
    (comp (ref "HAL_MANUALTOOLCHANGE")
      (value "HAL_MANUALTOOLCHANGE")
      (footprint "eagle-import:DUMMY")
      (libsource (lib "eagle-import") (part "HAL_MANUALTOOLCHANGE"))
    )
    (comp (ref "IOCONTROL.0")
      (value "IOCONTROL")
      (footprint "eagle-import:DUMMY")
      (libsource (lib "eagle-import") (part "IOCONTROL"))
    )
    (comp (ref "MOTION")
      (value "MOTION")
      (footprint "eagle-import:DUMMY")
      (libsource (lib "eagle-import") (part "MOTION"))
    )
    (comp (ref "HALUI.JOG.0")
      (value "HALUI.JOG")
      (footprint "eagle-import:DUMMY")
      (libsource (lib "eagle-import") (part "HALUI.JOG"))
    )
    (comp (ref "HALUI.JOG.1")
      (value "HALUI.JOG")
      (footprint "eagle-import:DUMMY")
      (libsource (lib "eagle-import") (part "HALUI.JOG"))
    )
    (comp (ref "HALUI.JOG.2")
      (value "HALUI.JOG")
      (footprint "eagle-import:DUMMY")
      (libsource (lib "eagle-import") (part "HALUI.JOG"))
    )
    (comp (ref "HALUI.JOG.3")
      (value "HALUI.JOG")
      (footprint "eagle-import:DUMMY")
      (libsource (lib "eagle-import") (part "HALUI.JOG"))
    )
  )
  (nets
    (net (code "1") (name "A-AMP-ENABLE") (class "Default")
      (node (ref "AXIS.3") (pin "P$22") (pinfunction "AMP-ENABLE-OUT_P$22") (pintype "output"))
      (node (ref "LOGIC.0") (pin "P$6") (pinfunction "IN-03_P$6") (pintype "input"))
      (node (ref "STEPGEN.3") (pin "P$15") (pinfunction "ENABLE_P$15") (pintype "input"))
    )
    (net (code "2") (name "A-ANALOG") (class "Default")
      (node (ref "HALUI.JOG.3") (pin "P$1") (pinfunction "ANALOG_P$1") (pintype "input"))
      (node (ref "MUX2.4") (pin "P$4") (pinfunction "OUT_P$4") (pintype "output"))
    )
    (net (code "3") (name "A-BUTTON-MINUS") (class "Default")
      (node (ref "AND2.7") (pin "P$1") (pinfunction "IN0_P$1") (pintype "input"))
      (node (ref "INPUT.0") (pin "P$61") (pinfunction "BTN-JOYSTICK_P$61") (pintype "output"))
      (node (ref "OR2.0") (pin "P$2") (pinfunction "IN0_P$2") (pintype "input"))
    )
    (net (code "4") (name "A-BUTTON-PLUS") (class "Default")
      (node (ref "AND2.8") (pin "P$1") (pinfunction "IN0_P$1") (pintype "input"))
      (node (ref "INPUT.0") (pin "P$67") (pinfunction "BTN-THUMB2_P$67") (pintype "output"))
      (node (ref "OR2.0") (pin "P$3") (pinfunction "IN1_P$3") (pintype "input"))
    )
    (net (code "5") (name "A-BUTTONS-ACTIVE") (class "Default")
      (node (ref "OR2.0") (pin "P$4") (pinfunction "OUT_P$4") (pintype "output"))
      (node (ref "OR2.1") (pin "P$2") (pinfunction "IN0_P$2") (pintype "input"))
      (node (ref "OR2.11") (pin "P$3") (pinfunction "IN1_P$3") (pintype "input"))
    )
    (net (code "6") (name "A-DIRECTION") (class "Default")
      (node (ref "PARPORT.0") (pin "P$41") (pinfunction "PIN-08-OUT_P$41") (pintype "input"))
      (node (ref "STEPGEN.3") (pin "P$14") (pinfunction "DIR_P$14") (pintype "output"))
    )
    (net (code "7") (name "A-DISABLE") (class "Default")
      (node (ref "AND2.13") (pin "P$2") (pinfunction "IN1_P$2") (pintype "input"))
      (node (ref "NOT.7") (pin "P$2") (pinfunction "OUT_P$2") (pintype "output"))
    )
    (net (code "8") (name "A-ENABLE") (class "Default")
      (node (ref "FLIPFLOP.3") (pin "P$3") (pinfunction "OUT_P$3") (pintype "output"))
      (node (ref "MUX2.4") (pin "P$5") (pinfunction "SEL_P$5") (pintype "input"))
      (node (ref "NOT.7") (pin "P$1") (pinfunction "IN_P$1") (pintype "input"))
      (node (ref "OR2.11") (pin "P$2") (pinfunction "IN0_P$2") (pintype "input"))
    )
    (net (code "9") (name "A-JOG") (class "Default")
      (node (ref "INPUT.0") (pin "P$47") (pinfunction "ABS-Z-POSITION_P$47") (pintype "output"))
      (node (ref "MUX2.4") (pin "P$3") (pinfunction "IN1_P$3") (pintype "input"))
    )
    (net (code "10") (name "A-KNOB-ACTIVE") (class "Default")
      (node (ref "AND2.15") (pin "P$2") (pinfunction "IN1_P$2") (pintype "input"))
      (node (ref "NOT.2") (pin "P$1") (pinfunction "IN_P$1") (pintype "input"))
      (node (ref "OR2.9") (pin "P$4") (pinfunction "OUT_P$4") (pintype "output"))
    )
    (net (code "11") (name "A-KNOB-INACTIVE") (class "Default")
      (node (ref "AND2.14") (pin "P$2") (pinfunction "IN1_P$2") (pintype "input"))
      (node (ref "NOT.2") (pin "P$2") (pinfunction "OUT_P$2") (pintype "output"))
    )
    (net (code "12") (name "A-SELECT") (class "Default")
      (node (ref "AND2.15") (pin "P$3") (pinfunction "OUT_P$3") (pintype "output"))
      (node (ref "AND2.16") (pin "P$1") (pinfunction "IN0_P$1") (pintype "input"))
    )
    (net (code "13") (name "A-SET") (class "Default")
      (node (ref "AND2.16") (pin "P$3") (pinfunction "OUT_P$3") (pintype "output"))
      (node (ref "FLIPFLOP.3") (pin "P$5") (pinfunction "SET_P$5") (pintype "input"))
    )
    (net (code "14") (name "A-STEP") (class "Default")
      (node (ref "PARPORT.0") (pin "P$42") (pinfunction "PIN-09-OUT_P$42") (pintype "input"))
      (node (ref "STEPGEN.3") (pin "P$18") (pinfunction "STEP_P$18") (pintype "output"))
    )
    (net (code "15") (name "ALL-AMPS-ENABLED") (class "Default")
      (node (ref "LOGIC.0") (pin "P$2") (pinfunction "AND_P$2") (pintype "output"))
      (node (ref "PARPORT.0") (pin "P$45") (pinfunction "PIN-17-OUT_P$45") (pintype "input"))
    )
    (net (code "16") (name "ANGULAR_MOTION") (class "Default")
      (node (ref "MUX2.0") (pin "P$5") (pinfunction "SEL_P$5") (pintype "input"))
      (node (ref "OR2.11") (pin "P$4") (pinfunction "OUT_P$4") (pintype "output"))
    )
    (net (code "17") (name "ANY-BUTTONS-ACTIVE") (class "Default")
      (node (ref "MUX4.0") (pin "P$7") (pinfunction "SEL0_P$7") (pintype "input"))
      (node (ref "OR2.12") (pin "P$4") (pinfunction "OUT_P$4") (pintype "output"))
    )
    (net (code "18") (name "AXIS-DISABLED-VALUE") (class "Default")
      (node (ref "CONSTANT.9") (pin "P$2") (pinfunction "OUT_P$2") (pintype "output"))
      (node (ref "MUX2.1") (pin "P$2") (pinfunction "IN0_P$2") (pintype "input"))
      (node (ref "MUX2.2") (pin "P$2") (pinfunction "IN0_P$2") (pintype "input"))
      (node (ref "MUX2.3") (pin "P$2") (pinfunction "IN0_P$2") (pintype "input"))
      (node (ref "MUX2.4") (pin "P$2") (pinfunction "IN0_P$2") (pintype "input"))
    )
    (net (code "19") (name "AZ-BUTTONS-ACTIVE") (class "Default")
      (node (ref "OR2.1") (pin "P$4") (pinfunction "OUT_P$4") (pintype "output"))
      (node (ref "OR2.12") (pin "P$3") (pinfunction "IN1_P$3") (pintype "input"))
      (node (ref "OR2.13") (pin "P$2") (pinfunction "IN0_P$2") (pintype "input"))
    )
    (net (code "20") (name "AZ-RESET") (class "Default")
      (node (ref "AND2.14") (pin "P$3") (pinfunction "OUT_P$3") (pintype "output"))
      (node (ref "FLIPFLOP.2") (pin "P$4") (pinfunction "RESET_P$4") (pintype "input"))
      (node (ref "FLIPFLOP.3") (pin "P$4") (pinfunction "RESET_P$4") (pintype "input"))
    )
    (net (code "21") (name "BASE-THREAD") (class "Default")
      (node (ref "4:STEPGEN") (pin "P$2") (pinfunction "PIN_THREAD_P$2") (pintype "bidirectional"))
      (node (ref "5:PWMGEN") (pin "P$2") (pinfunction "PIN_THREAD_P$2") (pintype "bidirectional"))
      (node (ref "BASE-THREAD") (pin "P$7") (pinfunction "__P$7") (pintype "output"))
      (node (ref "LOGIC.0") (pin "P$1") (pinfunction "PIN_THREAD_P$1") (pintype "bidirectional"))
      (node (ref "PARPORT.0") (pin "P$21") (pinfunction "PIN_THREAD_P$21") (pintype "bidirectional"))
      (node (ref "PARPORT.0") (pin "P$23") (pinfunction "PIN_THREAD_P$23") (pintype "bidirectional"))
      (node (ref "PARPORT.0") (pin "P$46") (pinfunction "PIN_THREAD_P$46") (pintype "bidirectional"))
    )
    (net (code "22") (name "BUTTON-CRAWL") (class "Default")
      (node (ref "MUX4.0") (pin "P$5") (pinfunction "IN3_P$5") (pintype "input"))
      (node (ref "SCALE.4") (pin "P$5") (pinfunction "OUT_P$5") (pintype "output"))
    )
    (net (code "23") (name "BUTTON-FAST") (class "Default")
      (node (ref "MUX4.0") (pin "P$3") (pinfunction "IN1_P$3") (pintype "input"))
      (node (ref "SCALE.2") (pin "P$5") (pinfunction "OUT_P$5") (pintype "output"))
      (node (ref "SCALE.4") (pin "P$3") (pinfunction "IN_P$3") (pintype "input"))
    )
    (net (code "24") (name "ESTOP-A") (class "Default")
      (node (ref "AND2.0") (pin "P$1") (pinfunction "IN0_P$1") (pintype "input"))
      (node (ref "INPUT.0") (pin "P$71") (pinfunction "BTN-TOP2_P$71") (pintype "output"))
    )
    (net (code "25") (name "ESTOP-B") (class "Default")
      (node (ref "AND2.0") (pin "P$2") (pinfunction "IN1_P$2") (pintype "input"))
      (node (ref "INPUT.0") (pin "P$49") (pinfunction "BTN-BASE_P$49") (pintype "output"))
    )
    (net (code "26") (name "ESTOP-OUT") (class "Default")
      (node (ref "IOCONTROL.0") (pin "P$11") (pinfunction "USER-ENABLE-OUT_P$11") (pintype "output"))
      (node (ref "IOCONTROL.0") (pin "P$3") (pinfunction "EMC-ENABLE-IN_P$3") (pintype "input"))
      (node (ref "PARPORT.0") (pin "P$34") (pinfunction "PIN-01-OUT_P$34") (pintype "input"))
    )
    (net (code "27") (name "HOMESWITCHES") (class "Default")
      (node (ref "AXIS.0") (pin "P$24") (pinfunction "HOME-SW-IN_P$24") (pintype "input"))
      (node (ref "AXIS.1") (pin "P$24") (pinfunction "HOME-SW-IN_P$24") (pintype "input"))
      (node (ref "AXIS.2") (pin "P$24") (pinfunction "HOME-SW-IN_P$24") (pintype "input"))
      (node (ref "AXIS.3") (pin "P$24") (pinfunction "HOME-SW-IN_P$24") (pintype "input"))
      (node (ref "PARPORT.0") (pin "P$25") (pinfunction "PIN-10-IN-NOT_P$25") (pintype "output"))
    )
    (net (code "28") (name "JOG-CRAWL") (class "Default")
      (node (ref "MUX4.0") (pin "P$8") (pinfunction "SEL1_P$8") (pintype "input"))
      (node (ref "TOGGLE.0") (pin "P$3") (pinfunction "OUT_P$3") (pintype "output"))
    )
    (net (code "29") (name "JOG-SPEED") (class "Default")
      (node (ref "HALUI") (pin "P$82") (pinfunction "JOG-SPEED_P$82") (pintype "input"))
      (node (ref "MUX4.0") (pin "P$6") (pinfunction "OUT_P$6") (pintype "output"))
    )
    (net (code "30") (name "KNOB-CRAWL") (class "Default")
      (node (ref "MUX4.0") (pin "P$4") (pinfunction "IN2_P$4") (pintype "input"))
      (node (ref "SCALE.3") (pin "P$5") (pinfunction "OUT_P$5") (pintype "output"))
    )
    (net (code "31") (name "KNOB-FAST") (class "Default")
      (node (ref "MUX4.0") (pin "P$2") (pinfunction "IN0_P$2") (pintype "input"))
      (node (ref "SCALE.1") (pin "P$5") (pinfunction "OUT_P$5") (pintype "output"))
      (node (ref "SCALE.3") (pin "P$3") (pinfunction "IN_P$3") (pintype "input"))
    )
    (net (code "32") (name "MANUAL-MODE") (class "Default")
      (node (ref "HALUI") (pin "P$72") (pinfunction "MODE.MANUAL_P$72") (pintype "input"))
      (node (ref "INPUT.0") (pin "P$53") (pinfunction "BTN-BASE3_P$53") (pintype "output"))
    )
    (net (code "33") (name "Net-(AND2.0B-OUT)") (class "Default")
      (node (ref "AND2.0") (pin "P$3") (pinfunction "OUT_P$3") (pintype "output"))
      (node (ref "HALUI") (pin "P$2") (pinfunction "ESTOP.ACTIVATE_P$2") (pintype "input"))
    )
    (net (code "34") (name "Net-(AND2.1B-IN1)") (class "Default")
      (node (ref "AND2.1") (pin "P$2") (pinfunction "IN1_P$2") (pintype "input"))
      (node (ref "AND2.2") (pin "P$2") (pinfunction "IN1_P$2") (pintype "input"))
      (node (ref "AND2.3") (pin "P$2") (pinfunction "IN1_P$2") (pintype "input"))
      (node (ref "AND2.4") (pin "P$2") (pinfunction "IN1_P$2") (pintype "input"))
      (node (ref "AND2.5") (pin "P$2") (pinfunction "IN1_P$2") (pintype "input"))
      (node (ref "AND2.6") (pin "P$2") (pinfunction "IN1_P$2") (pintype "input"))
      (node (ref "AND2.7") (pin "P$2") (pinfunction "IN1_P$2") (pintype "input"))
      (node (ref "AND2.8") (pin "P$2") (pinfunction "IN1_P$2") (pintype "input"))
      (node (ref "TIMEDELAY.0") (pin "P$5") (pinfunction "OUT_P$5") (pintype "output"))
    )
    (net (code "35") (name "Net-(AND2.1B-OUT)") (class "Default")
      (node (ref "AND2.1") (pin "P$3") (pinfunction "OUT_P$3") (pintype "output"))
      (node (ref "HALUI.JOG.0") (pin "P$2") (pinfunction "MINUS_P$2") (pintype "input"))
    )
    (net (code "36") (name "Net-(AND2.2B-OUT)") (class "Default")
      (node (ref "AND2.2") (pin "P$3") (pinfunction "OUT_P$3") (pintype "output"))
      (node (ref "HALUI.JOG.0") (pin "P$3") (pinfunction "PLUS_P$3") (pintype "input"))
    )
    (net (code "37") (name "Net-(AND2.3B-OUT)") (class "Default")
      (node (ref "AND2.3") (pin "P$3") (pinfunction "OUT_P$3") (pintype "output"))
      (node (ref "HALUI.JOG.1") (pin "P$2") (pinfunction "MINUS_P$2") (pintype "input"))
    )
    (net (code "38") (name "Net-(AND2.4B-OUT)") (class "Default")
      (node (ref "AND2.4") (pin "P$3") (pinfunction "OUT_P$3") (pintype "output"))
      (node (ref "HALUI.JOG.1") (pin "P$3") (pinfunction "PLUS_P$3") (pintype "input"))
    )
    (net (code "39") (name "Net-(AND2.5B-OUT)") (class "Default")
      (node (ref "AND2.5") (pin "P$3") (pinfunction "OUT_P$3") (pintype "output"))
      (node (ref "HALUI.JOG.2") (pin "P$2") (pinfunction "MINUS_P$2") (pintype "input"))
    )
    (net (code "40") (name "Net-(AND2.6B-OUT)") (class "Default")
      (node (ref "AND2.6") (pin "P$3") (pinfunction "OUT_P$3") (pintype "output"))
      (node (ref "HALUI.JOG.2") (pin "P$3") (pinfunction "PLUS_P$3") (pintype "input"))
    )
    (net (code "41") (name "Net-(AND2.7B-OUT)") (class "Default")
      (node (ref "AND2.7") (pin "P$3") (pinfunction "OUT_P$3") (pintype "output"))
      (node (ref "HALUI.JOG.3") (pin "P$2") (pinfunction "MINUS_P$2") (pintype "input"))
    )
    (net (code "42") (name "Net-(AND2.8B-OUT)") (class "Default")
      (node (ref "AND2.8") (pin "P$3") (pinfunction "OUT_P$3") (pintype "output"))
      (node (ref "HALUI.JOG.3") (pin "P$3") (pinfunction "PLUS_P$3") (pintype "input"))
    )
    (net (code "43") (name "Net-(AXIS.0V-MOTOR-POS-CMD)") (class "Default")
      (node (ref "AXIS.0") (pin "P$33") (pinfunction "MOTOR-POS-CMD_P$33") (pintype "output"))
      (node (ref "STEPGEN.0") (pin "P$16") (pinfunction "POSITION-CMD_P$16") (pintype "input"))
    )
    (net (code "44") (name "Net-(AXIS.0V-MOTOR-POS-FB)") (class "Default")
      (node (ref "AXIS.0") (pin "P$34") (pinfunction "MOTOR-POS-FB_P$34") (pintype "input"))
      (node (ref "STEPGEN.0") (pin "P$17") (pinfunction "POSITION-FB_P$17") (pintype "output"))
    )
    (net (code "45") (name "Net-(AXIS.1V-MOTOR-POS-CMD)") (class "Default")
      (node (ref "AXIS.1") (pin "P$33") (pinfunction "MOTOR-POS-CMD_P$33") (pintype "output"))
      (node (ref "STEPGEN.1") (pin "P$16") (pinfunction "POSITION-CMD_P$16") (pintype "input"))
    )
    (net (code "46") (name "Net-(AXIS.1V-MOTOR-POS-FB)") (class "Default")
      (node (ref "AXIS.1") (pin "P$34") (pinfunction "MOTOR-POS-FB_P$34") (pintype "input"))
      (node (ref "STEPGEN.1") (pin "P$17") (pinfunction "POSITION-FB_P$17") (pintype "output"))
    )
    (net (code "47") (name "Net-(AXIS.2V-MOTOR-POS-CMD)") (class "Default")
      (node (ref "AXIS.2") (pin "P$33") (pinfunction "MOTOR-POS-CMD_P$33") (pintype "output"))
      (node (ref "STEPGEN.2") (pin "P$16") (pinfunction "POSITION-CMD_P$16") (pintype "input"))
    )
    (net (code "48") (name "Net-(AXIS.2V-MOTOR-POS-FB)") (class "Default")
      (node (ref "AXIS.2") (pin "P$34") (pinfunction "MOTOR-POS-FB_P$34") (pintype "input"))
      (node (ref "STEPGEN.2") (pin "P$17") (pinfunction "POSITION-FB_P$17") (pintype "output"))
    )
    (net (code "49") (name "Net-(AXIS.3V-MOTOR-POS-CMD)") (class "Default")
      (node (ref "AXIS.3") (pin "P$33") (pinfunction "MOTOR-POS-CMD_P$33") (pintype "output"))
      (node (ref "STEPGEN.3") (pin "P$16") (pinfunction "POSITION-CMD_P$16") (pintype "input"))
    )
    (net (code "50") (name "Net-(AXIS.3V-MOTOR-POS-FB)") (class "Default")
      (node (ref "AXIS.3") (pin "P$34") (pinfunction "MOTOR-POS-FB_P$34") (pintype "input"))
      (node (ref "STEPGEN.3") (pin "P$17") (pinfunction "POSITION-FB_P$17") (pintype "output"))
    )
    (net (code "51") (name "Net-(CONSTANT.0B-OUT)") (class "Default")
      (node (ref "CONSTANT.0") (pin "P$2") (pinfunction "OUT_P$2") (pintype "output"))
      (node (ref "HALUI") (pin "P$81") (pinfunction "JOG-DEADBAND_P$81") (pintype "input"))
    )
    (net (code "52") (name "Net-(CONSTANT.1B-OUT)") (class "Default")
      (node (ref "CONSTANT.1") (pin "P$2") (pinfunction "OUT_P$2") (pintype "output"))
      (node (ref "CONV-FLOAT-S32.0") (pin "P$3") (pinfunction "IN_P$3") (pintype "input"))
    )
    (net (code "53") (name "Net-(CONSTANT.2B-OUT)") (class "Default")
      (node (ref "CONSTANT.2") (pin "P$2") (pinfunction "OUT_P$2") (pintype "output"))
      (node (ref "MUX2.0") (pin "P$2") (pinfunction "IN0_P$2") (pintype "input"))
    )
    (net (code "54") (name "Net-(CONSTANT.3B-OUT)") (class "Default")
      (node (ref "CONSTANT.3") (pin "P$2") (pinfunction "OUT_P$2") (pintype "output"))
      (node (ref "MUX2.0") (pin "P$3") (pinfunction "IN1_P$3") (pintype "input"))
    )
    (net (code "55") (name "Net-(CONSTANT.4B-OUT)") (class "Default")
      (node (ref "CONSTANT.4") (pin "P$2") (pinfunction "OUT_P$2") (pintype "output"))
      (node (ref "SCALE.0") (pin "P$2") (pinfunction "GAIN_P$2") (pintype "input"))
    )
    (net (code "56") (name "Net-(CONSTANT.5B-OUT)") (class "Default")
      (node (ref "CONSTANT.5") (pin "P$2") (pinfunction "OUT_P$2") (pintype "output"))
      (node (ref "SCALE.1") (pin "P$2") (pinfunction "GAIN_P$2") (pintype "input"))
    )
    (net (code "57") (name "Net-(CONSTANT.6B-OUT)") (class "Default")
      (node (ref "CONSTANT.6") (pin "P$2") (pinfunction "OUT_P$2") (pintype "output"))
      (node (ref "SCALE.2") (pin "P$2") (pinfunction "GAIN_P$2") (pintype "input"))
    )
    (net (code "58") (name "Net-(CONSTANT.7B-OUT)") (class "Default")
      (node (ref "CONSTANT.7") (pin "P$2") (pinfunction "OUT_P$2") (pintype "output"))
      (node (ref "SCALE.3") (pin "P$2") (pinfunction "GAIN_P$2") (pintype "input"))
    )
    (net (code "59") (name "Net-(CONSTANT.8B-OUT)") (class "Default")
      (node (ref "CONSTANT.8") (pin "P$2") (pinfunction "OUT_P$2") (pintype "output"))
      (node (ref "SCALE.4") (pin "P$2") (pinfunction "GAIN_P$2") (pintype "input"))
    )
    (net (code "60") (name "Net-(CONSTANT.10B-OUT)") (class "Default")
      (node (ref "CONSTANT.10") (pin "P$2") (pinfunction "OUT_P$2") (pintype "output"))
      (node (ref "SCALE.5") (pin "P$2") (pinfunction "GAIN_P$2") (pintype "input"))
      (node (ref "SCALE.6") (pin "P$2") (pinfunction "GAIN_P$2") (pintype "input"))
    )
    (net (code "61") (name "Net-(CONSTANT.11B-OUT)") (class "Default")
      (node (ref "CONSTANT.11") (pin "P$2") (pinfunction "OUT_P$2") (pintype "output"))
      (node (ref "TIMEDELAY.0") (pin "P$4") (pinfunction "ON-DELAY_P$4") (pintype "input"))
    )
    (net (code "62") (name "Net-(CONSTANT.12B-OUT)") (class "Default")
      (node (ref "CONSTANT.12") (pin "P$2") (pinfunction "OUT_P$2") (pintype "output"))
      (node (ref "TIMEDELAY.0") (pin "P$3") (pinfunction "OFF-DELAY_P$3") (pintype "input"))
    )
    (net (code "63") (name "Net-(CONV-FLOAT-S32.0C-OUT)") (class "Default")
      (node (ref "CONV-FLOAT-S32.0") (pin "P$4") (pinfunction "OUT_P$4") (pintype "output"))
      (node (ref "INPUT.0") (pin "P$18") (pinfunction "ABS-RZ-FLAT_P$18") (pintype "input"))
      (node (ref "INPUT.0") (pin "P$26") (pinfunction "ABS-X-FLAT_P$26") (pintype "input"))
      (node (ref "INPUT.0") (pin "P$34") (pinfunction "ABS-Y-FLAT_P$34") (pintype "input"))
      (node (ref "INPUT.0") (pin "P$42") (pinfunction "ABS-Z-FLAT_P$42") (pintype "input"))
    )
    (net (code "64") (name "Net-(INPUT.0A-ABS-RZ-IS-NEG)") (class "Default")
      (node (ref "INPUT.0") (pin "P$20") (pinfunction "ABS-RZ-IS-NEG_P$20") (pintype "output"))
      (node (ref "OR2.10") (pin "P$3") (pinfunction "IN1_P$3") (pintype "input"))
    )
    (net (code "65") (name "Net-(INPUT.0A-ABS-RZ-IS-POS)") (class "Default")
      (node (ref "INPUT.0") (pin "P$21") (pinfunction "ABS-RZ-IS-POS_P$21") (pintype "output"))
      (node (ref "OR2.10") (pin "P$2") (pinfunction "IN0_P$2") (pintype "input"))
    )
    (net (code "66") (name "Net-(INPUT.0A-ABS-X-IS-NEG)") (class "Default")
      (node (ref "INPUT.0") (pin "P$28") (pinfunction "ABS-X-IS-NEG_P$28") (pintype "output"))
      (node (ref "OR2.7") (pin "P$3") (pinfunction "IN1_P$3") (pintype "input"))
    )
    (net (code "67") (name "Net-(INPUT.0A-ABS-X-IS-POS)") (class "Default")
      (node (ref "INPUT.0") (pin "P$29") (pinfunction "ABS-X-IS-POS_P$29") (pintype "output"))
      (node (ref "OR2.7") (pin "P$2") (pinfunction "IN0_P$2") (pintype "input"))
    )
    (net (code "68") (name "Net-(INPUT.0A-ABS-Y-IS-NEG)") (class "Default")
      (node (ref "INPUT.0") (pin "P$36") (pinfunction "ABS-Y-IS-NEG_P$36") (pintype "output"))
      (node (ref "OR2.8") (pin "P$3") (pinfunction "IN1_P$3") (pintype "input"))
    )
    (net (code "69") (name "Net-(INPUT.0A-ABS-Y-IS-POS)") (class "Default")
      (node (ref "INPUT.0") (pin "P$37") (pinfunction "ABS-Y-IS-POS_P$37") (pintype "output"))
      (node (ref "OR2.8") (pin "P$2") (pinfunction "IN0_P$2") (pintype "input"))
    )
    (net (code "70") (name "Net-(INPUT.0A-ABS-Z-IS-NEG)") (class "Default")
      (node (ref "INPUT.0") (pin "P$44") (pinfunction "ABS-Z-IS-NEG_P$44") (pintype "output"))
      (node (ref "OR2.9") (pin "P$3") (pinfunction "IN1_P$3") (pintype "input"))
    )
    (net (code "71") (name "Net-(INPUT.0A-ABS-Z-IS-POS)") (class "Default")
      (node (ref "INPUT.0") (pin "P$45") (pinfunction "ABS-Z-IS-POS_P$45") (pintype "output"))
      (node (ref "OR2.9") (pin "P$2") (pinfunction "IN0_P$2") (pintype "input"))
    )
    (net (code "72") (name "Net-(INPUT.0B-BTN-BASE5)") (class "Default")
      (node (ref "INPUT.0") (pin "P$57") (pinfunction "BTN-BASE5_P$57") (pintype "output"))
      (node (ref "OR2.3") (pin "P$2") (pinfunction "IN0_P$2") (pintype "input"))
    )
    (net (code "73") (name "Net-(INPUT.0B-BTN-BASE6)") (class "Default")
      (node (ref "INPUT.0") (pin "P$59") (pinfunction "BTN-BASE6_P$59") (pintype "output"))
      (node (ref "OR2.3") (pin "P$3") (pinfunction "IN1_P$3") (pintype "input"))
    )
    (net (code "74") (name "Net-(OR2.3B-OUT)") (class "Default")
      (node (ref "OR2.3") (pin "P$4") (pinfunction "OUT_P$4") (pintype "output"))
      (node (ref "TOGGLE.0") (pin "P$2") (pinfunction "IN_P$2") (pintype "input"))
    )
    (net (code "75") (name "Net-(OR2.4B-OUT)") (class "Default")
      (node (ref "OR2.4") (pin "P$4") (pinfunction "OUT_P$4") (pintype "output"))
      (node (ref "OR2.5") (pin "P$2") (pinfunction "IN0_P$2") (pintype "input"))
    )
    (net (code "76") (name "Net-(OR2.5B-IN1)") (class "Default")
      (node (ref "OR2.5") (pin "P$3") (pinfunction "IN1_P$3") (pintype "input"))
      (node (ref "OR2.6") (pin "P$4") (pinfunction "OUT_P$4") (pintype "output"))
    )
    (net (code "77") (name "Net-(PARAMETER0-P$2)") (class "Default")
      (node (ref "PARAMETER0") (pin "P$1") (pinfunction "P$2_P$1") (pintype "output"))
      (node (ref "PARPORT.0") (pin "P$22") (pinfunction "PIN_PARAMETER_P$22") (pintype "bidirectional"))
    )
    (net (code "78") (name "Net-(PARAMETER1-P$2)") (class "Default")
      (node (ref "PARAMETER1") (pin "P$1") (pinfunction "P$2_P$1") (pintype "output"))
      (node (ref "STEPGEN.0") (pin "P$6") (pinfunction "PIN_PARAMETER_P$6") (pintype "bidirectional"))
    )
    (net (code "79") (name "Net-(PARAMETER2-P$2)") (class "Default")
      (node (ref "PARAMETER2") (pin "P$1") (pinfunction "P$2_P$1") (pintype "output"))
      (node (ref "STEPGEN.0") (pin "P$5") (pinfunction "PIN_PARAMETER_P$5") (pintype "bidirectional"))
    )
    (net (code "80") (name "Net-(PARAMETER3-P$2)") (class "Default")
      (node (ref "PARAMETER3") (pin "P$1") (pinfunction "P$2_P$1") (pintype "output"))
      (node (ref "STEPGEN.0") (pin "P$2") (pinfunction "PIN_PARAMETER_P$2") (pintype "bidirectional"))
    )
    (net (code "81") (name "Net-(PARAMETER4-P$2)") (class "Default")
      (node (ref "PARAMETER4") (pin "P$1") (pinfunction "P$2_P$1") (pintype "output"))
      (node (ref "STEPGEN.0") (pin "P$3") (pinfunction "PIN_PARAMETER_P$3") (pintype "bidirectional"))
    )
    (net (code "82") (name "Net-(PARAMETER5-P$2)") (class "Default")
      (node (ref "PARAMETER5") (pin "P$1") (pinfunction "P$2_P$1") (pintype "output"))
      (node (ref "STEPGEN.0") (pin "P$9") (pinfunction "PIN_PARAMETER_P$9") (pintype "bidirectional"))
    )
    (net (code "83") (name "Net-(PARAMETER6-P$2)") (class "Default")
      (node (ref "PARAMETER6") (pin "P$1") (pinfunction "P$2_P$1") (pintype "output"))
      (node (ref "STEPGEN.0") (pin "P$10") (pinfunction "PIN_PARAMETER_P$10") (pintype "bidirectional"))
    )
    (net (code "84") (name "Net-(PARAMETER7-P$2)") (class "Default")
      (node (ref "PARAMETER7") (pin "P$1") (pinfunction "P$2_P$1") (pintype "output"))
      (node (ref "STEPGEN.0") (pin "P$7") (pinfunction "PIN_PARAMETER_P$7") (pintype "bidirectional"))
    )
    (net (code "85") (name "Net-(PARAMETER8-P$2)") (class "Default")
      (node (ref "PARAMETER8") (pin "P$1") (pinfunction "P$2_P$1") (pintype "output"))
      (node (ref "PARPORT.0") (pin "P$13") (pinfunction "PIN_PARAMETER_P$13") (pintype "bidirectional"))
      (node (ref "PARPORT.0") (pin "P$17") (pinfunction "PIN_PARAMETER_P$17") (pintype "bidirectional"))
      (node (ref "PARPORT.0") (pin "P$5") (pinfunction "PIN_PARAMETER_P$5") (pintype "bidirectional"))
      (node (ref "PARPORT.0") (pin "P$50") (pinfunction "PIN_PARAMETER_P$50") (pintype "bidirectional"))
      (node (ref "PARPORT.0") (pin "P$9") (pinfunction "PIN_PARAMETER_P$9") (pintype "bidirectional"))
    )
    (net (code "86") (name "Net-(PARAMETER9-P$2)") (class "Default")
      (node (ref "PARAMETER9") (pin "P$1") (pinfunction "P$2_P$1") (pintype "output"))
      (node (ref "STEPGEN.1") (pin "P$6") (pinfunction "PIN_PARAMETER_P$6") (pintype "bidirectional"))
    )
    (net (code "87") (name "Net-(PARAMETER10-P$2)") (class "Default")
      (node (ref "PARAMETER10") (pin "P$1") (pinfunction "P$2_P$1") (pintype "output"))
      (node (ref "STEPGEN.1") (pin "P$5") (pinfunction "PIN_PARAMETER_P$5") (pintype "bidirectional"))
    )
    (net (code "88") (name "Net-(PARAMETER11-P$2)") (class "Default")
      (node (ref "PARAMETER11") (pin "P$1") (pinfunction "P$2_P$1") (pintype "output"))
      (node (ref "STEPGEN.1") (pin "P$2") (pinfunction "PIN_PARAMETER_P$2") (pintype "bidirectional"))
    )
    (net (code "89") (name "Net-(PARAMETER12-P$2)") (class "Default")
      (node (ref "PARAMETER12") (pin "P$1") (pinfunction "P$2_P$1") (pintype "output"))
      (node (ref "STEPGEN.1") (pin "P$3") (pinfunction "PIN_PARAMETER_P$3") (pintype "bidirectional"))
    )
    (net (code "90") (name "Net-(PARAMETER13-P$2)") (class "Default")
      (node (ref "PARAMETER13") (pin "P$1") (pinfunction "P$2_P$1") (pintype "output"))
      (node (ref "STEPGEN.1") (pin "P$9") (pinfunction "PIN_PARAMETER_P$9") (pintype "bidirectional"))
    )
    (net (code "91") (name "Net-(PARAMETER14-P$2)") (class "Default")
      (node (ref "PARAMETER14") (pin "P$1") (pinfunction "P$2_P$1") (pintype "output"))
      (node (ref "STEPGEN.1") (pin "P$10") (pinfunction "PIN_PARAMETER_P$10") (pintype "bidirectional"))
    )
    (net (code "92") (name "Net-(PARAMETER15-P$2)") (class "Default")
      (node (ref "PARAMETER15") (pin "P$1") (pinfunction "P$2_P$1") (pintype "output"))
      (node (ref "STEPGEN.1") (pin "P$7") (pinfunction "PIN_PARAMETER_P$7") (pintype "bidirectional"))
    )
    (net (code "93") (name "Net-(PARAMETER16-P$2)") (class "Default")
      (node (ref "PARAMETER16") (pin "P$1") (pinfunction "P$2_P$1") (pintype "output"))
      (node (ref "STEPGEN.2") (pin "P$6") (pinfunction "PIN_PARAMETER_P$6") (pintype "bidirectional"))
    )
    (net (code "94") (name "Net-(PARAMETER17-P$2)") (class "Default")
      (node (ref "PARAMETER17") (pin "P$1") (pinfunction "P$2_P$1") (pintype "output"))
      (node (ref "STEPGEN.2") (pin "P$5") (pinfunction "PIN_PARAMETER_P$5") (pintype "bidirectional"))
    )
    (net (code "95") (name "Net-(PARAMETER18-P$2)") (class "Default")
      (node (ref "PARAMETER18") (pin "P$1") (pinfunction "P$2_P$1") (pintype "output"))
      (node (ref "STEPGEN.2") (pin "P$2") (pinfunction "PIN_PARAMETER_P$2") (pintype "bidirectional"))
    )
    (net (code "96") (name "Net-(PARAMETER19-P$2)") (class "Default")
      (node (ref "PARAMETER19") (pin "P$1") (pinfunction "P$2_P$1") (pintype "output"))
      (node (ref "STEPGEN.2") (pin "P$3") (pinfunction "PIN_PARAMETER_P$3") (pintype "bidirectional"))
    )
    (net (code "97") (name "Net-(PARAMETER20-P$2)") (class "Default")
      (node (ref "PARAMETER20") (pin "P$1") (pinfunction "P$2_P$1") (pintype "output"))
      (node (ref "STEPGEN.2") (pin "P$9") (pinfunction "PIN_PARAMETER_P$9") (pintype "bidirectional"))
    )
    (net (code "98") (name "Net-(PARAMETER21-P$2)") (class "Default")
      (node (ref "PARAMETER21") (pin "P$1") (pinfunction "P$2_P$1") (pintype "output"))
      (node (ref "STEPGEN.2") (pin "P$10") (pinfunction "PIN_PARAMETER_P$10") (pintype "bidirectional"))
    )
    (net (code "99") (name "Net-(PARAMETER22-P$2)") (class "Default")
      (node (ref "PARAMETER22") (pin "P$1") (pinfunction "P$2_P$1") (pintype "output"))
      (node (ref "STEPGEN.2") (pin "P$7") (pinfunction "PIN_PARAMETER_P$7") (pintype "bidirectional"))
    )
    (net (code "100") (name "Net-(PARAMETER23-P$2)") (class "Default")
      (node (ref "PARAMETER23") (pin "P$1") (pinfunction "P$2_P$1") (pintype "output"))
      (node (ref "STEPGEN.3") (pin "P$6") (pinfunction "PIN_PARAMETER_P$6") (pintype "bidirectional"))
    )
    (net (code "101") (name "Net-(PARAMETER24-P$2)") (class "Default")
      (node (ref "PARAMETER24") (pin "P$1") (pinfunction "P$2_P$1") (pintype "output"))
      (node (ref "STEPGEN.3") (pin "P$5") (pinfunction "PIN_PARAMETER_P$5") (pintype "bidirectional"))
    )
    (net (code "102") (name "Net-(PARAMETER25-P$2)") (class "Default")
      (node (ref "PARAMETER25") (pin "P$1") (pinfunction "P$2_P$1") (pintype "output"))
      (node (ref "STEPGEN.3") (pin "P$2") (pinfunction "PIN_PARAMETER_P$2") (pintype "bidirectional"))
    )
    (net (code "103") (name "Net-(PARAMETER26-P$2)") (class "Default")
      (node (ref "PARAMETER26") (pin "P$1") (pinfunction "P$2_P$1") (pintype "output"))
      (node (ref "STEPGEN.3") (pin "P$3") (pinfunction "PIN_PARAMETER_P$3") (pintype "bidirectional"))
    )
    (net (code "104") (name "Net-(PARAMETER27-P$2)") (class "Default")
      (node (ref "PARAMETER27") (pin "P$1") (pinfunction "P$2_P$1") (pintype "output"))
      (node (ref "STEPGEN.3") (pin "P$9") (pinfunction "PIN_PARAMETER_P$9") (pintype "bidirectional"))
    )
    (net (code "105") (name "Net-(PARAMETER28-P$2)") (class "Default")
      (node (ref "PARAMETER28") (pin "P$1") (pinfunction "P$2_P$1") (pintype "output"))
      (node (ref "STEPGEN.3") (pin "P$10") (pinfunction "PIN_PARAMETER_P$10") (pintype "bidirectional"))
    )
    (net (code "106") (name "Net-(PARAMETER29-P$2)") (class "Default")
      (node (ref "PARAMETER29") (pin "P$1") (pinfunction "P$2_P$1") (pintype "output"))
      (node (ref "STEPGEN.3") (pin "P$7") (pinfunction "PIN_PARAMETER_P$7") (pintype "bidirectional"))
    )
    (net (code "107") (name "Net-(PARAMETER30-P$2)") (class "Default")
      (node (ref "PARAMETER30") (pin "P$1") (pinfunction "P$2_P$1") (pintype "output"))
      (node (ref "PARPORT.0") (pin "P$10") (pinfunction "PIN_PARAMETER_P$10") (pintype "bidirectional"))
      (node (ref "PARPORT.0") (pin "P$6") (pinfunction "PIN_PARAMETER_P$6") (pintype "bidirectional"))
    )
    (net (code "108") (name "PROBE-IN") (class "Default")
      (node (ref "MOTION") (pin "P$23") (pinfunction "PROBE-INPUT_P$23") (pintype "input"))
      (node (ref "PARPORT.0") (pin "P$33") (pinfunction "PIN-15-IN-NOT_P$33") (pintype "output"))
    )
    (net (code "109") (name "PROGRAM-RESUME") (class "Default")
      (node (ref "HALUI") (pin "P$43") (pinfunction "PROGRAM.RESUME_P$43") (pintype "input"))
      (node (ref "INPUT.0") (pin "P$55") (pinfunction "BTN-BASE4_P$55") (pintype "output"))
    )
    (net (code "110") (name "RESET-ESTOP") (class "Default")
      (node (ref "HALUI") (pin "P$4") (pinfunction "ESTOP.RESET_P$4") (pintype "input"))
      (node (ref "INPUT.0") (pin "P$51") (pinfunction "BTN-BASE2_P$51") (pintype "output"))
    )
    (net (code "111") (name "SERVO-THREAD") (class "Default")
      (node (ref "1:MOTION") (pin "P$1") (pinfunction "PIN_THREAD_P$1") (pintype "bidirectional"))
      (node (ref "1:MOTION") (pin "P$2") (pinfunction "PIN_THREAD_P$2") (pintype "bidirectional"))
      (node (ref "4:STEPGEN") (pin "P$1") (pinfunction "PIN_THREAD_P$1") (pintype "bidirectional"))
      (node (ref "4:STEPGEN") (pin "P$3") (pinfunction "PIN_THREAD_P$3") (pintype "bidirectional"))
      (node (ref "5:PWMGEN") (pin "P$1") (pinfunction "PIN_THREAD_P$1") (pintype "bidirectional"))
      (node (ref "AND2.0") (pin "P$4") (pinfunction "PIN_THREAD_P$4") (pintype "bidirectional"))
      (node (ref "AND2.1") (pin "P$4") (pinfunction "PIN_THREAD_P$4") (pintype "bidirectional"))
      (node (ref "AND2.10") (pin "P$4") (pinfunction "PIN_THREAD_P$4") (pintype "bidirectional"))
      (node (ref "AND2.11") (pin "P$4") (pinfunction "PIN_THREAD_P$4") (pintype "bidirectional"))
      (node (ref "AND2.12") (pin "P$4") (pinfunction "PIN_THREAD_P$4") (pintype "bidirectional"))
      (node (ref "AND2.13") (pin "P$4") (pinfunction "PIN_THREAD_P$4") (pintype "bidirectional"))
      (node (ref "AND2.14") (pin "P$4") (pinfunction "PIN_THREAD_P$4") (pintype "bidirectional"))
      (node (ref "AND2.15") (pin "P$4") (pinfunction "PIN_THREAD_P$4") (pintype "bidirectional"))
      (node (ref "AND2.16") (pin "P$4") (pinfunction "PIN_THREAD_P$4") (pintype "bidirectional"))
      (node (ref "AND2.2") (pin "P$4") (pinfunction "PIN_THREAD_P$4") (pintype "bidirectional"))
      (node (ref "AND2.3") (pin "P$4") (pinfunction "PIN_THREAD_P$4") (pintype "bidirectional"))
      (node (ref "AND2.4") (pin "P$4") (pinfunction "PIN_THREAD_P$4") (pintype "bidirectional"))
      (node (ref "AND2.5") (pin "P$4") (pinfunction "PIN_THREAD_P$4") (pintype "bidirectional"))
      (node (ref "AND2.6") (pin "P$4") (pinfunction "PIN_THREAD_P$4") (pintype "bidirectional"))
      (node (ref "AND2.7") (pin "P$4") (pinfunction "PIN_THREAD_P$4") (pintype "bidirectional"))
      (node (ref "AND2.8") (pin "P$4") (pinfunction "PIN_THREAD_P$4") (pintype "bidirectional"))
      (node (ref "AND2.9") (pin "P$4") (pinfunction "PIN_THREAD_P$4") (pintype "bidirectional"))
      (node (ref "CONSTANT.0") (pin "P$1") (pinfunction "PIN_THREAD_P$1") (pintype "bidirectional"))
      (node (ref "CONSTANT.1") (pin "P$1") (pinfunction "PIN_THREAD_P$1") (pintype "bidirectional"))
      (node (ref "CONSTANT.10") (pin "P$1") (pinfunction "PIN_THREAD_P$1") (pintype "bidirectional"))
      (node (ref "CONSTANT.11") (pin "P$1") (pinfunction "PIN_THREAD_P$1") (pintype "bidirectional"))
      (node (ref "CONSTANT.12") (pin "P$1") (pinfunction "PIN_THREAD_P$1") (pintype "bidirectional"))
      (node (ref "CONSTANT.2") (pin "P$1") (pinfunction "PIN_THREAD_P$1") (pintype "bidirectional"))
      (node (ref "CONSTANT.3") (pin "P$1") (pinfunction "PIN_THREAD_P$1") (pintype "bidirectional"))
      (node (ref "CONSTANT.4") (pin "P$1") (pinfunction "PIN_THREAD_P$1") (pintype "bidirectional"))
      (node (ref "CONSTANT.5") (pin "P$1") (pinfunction "PIN_THREAD_P$1") (pintype "bidirectional"))
      (node (ref "CONSTANT.6") (pin "P$1") (pinfunction "PIN_THREAD_P$1") (pintype "bidirectional"))
      (node (ref "CONSTANT.7") (pin "P$1") (pinfunction "PIN_THREAD_P$1") (pintype "bidirectional"))
      (node (ref "CONSTANT.8") (pin "P$1") (pinfunction "PIN_THREAD_P$1") (pintype "bidirectional"))
      (node (ref "CONSTANT.9") (pin "P$1") (pinfunction "PIN_THREAD_P$1") (pintype "bidirectional"))
      (node (ref "CONV-FLOAT-S32.0") (pin "P$1") (pinfunction "PIN_THREAD_P$1") (pintype "bidirectional"))
      (node (ref "FLIPFLOP.0") (pin "P$6") (pinfunction "PIN_THREAD_P$6") (pintype "bidirectional"))
      (node (ref "FLIPFLOP.1") (pin "P$6") (pinfunction "PIN_THREAD_P$6") (pintype "bidirectional"))
      (node (ref "FLIPFLOP.2") (pin "P$6") (pinfunction "PIN_THREAD_P$6") (pintype "bidirectional"))
      (node (ref "FLIPFLOP.3") (pin "P$6") (pinfunction "PIN_THREAD_P$6") (pintype "bidirectional"))
      (node (ref "MUX2.0") (pin "P$1") (pinfunction "PIN_THREAD_P$1") (pintype "bidirectional"))
      (node (ref "MUX2.1") (pin "P$1") (pinfunction "PIN_THREAD_P$1") (pintype "bidirectional"))
      (node (ref "MUX2.2") (pin "P$1") (pinfunction "PIN_THREAD_P$1") (pintype "bidirectional"))
      (node (ref "MUX2.3") (pin "P$1") (pinfunction "PIN_THREAD_P$1") (pintype "bidirectional"))
      (node (ref "MUX2.4") (pin "P$1") (pinfunction "PIN_THREAD_P$1") (pintype "bidirectional"))
      (node (ref "MUX4.0") (pin "P$1") (pinfunction "PIN_THREAD_P$1") (pintype "bidirectional"))
      (node (ref "NOT.0") (pin "P$3") (pinfunction "PIN_THREAD_P$3") (pintype "bidirectional"))
      (node (ref "NOT.1") (pin "P$3") (pinfunction "PIN_THREAD_P$3") (pintype "bidirectional"))
      (node (ref "NOT.2") (pin "P$3") (pinfunction "PIN_THREAD_P$3") (pintype "bidirectional"))
      (node (ref "NOT.3") (pin "P$3") (pinfunction "PIN_THREAD_P$3") (pintype "bidirectional"))
      (node (ref "NOT.4") (pin "P$3") (pinfunction "PIN_THREAD_P$3") (pintype "bidirectional"))
      (node (ref "NOT.5") (pin "P$3") (pinfunction "PIN_THREAD_P$3") (pintype "bidirectional"))
      (node (ref "NOT.6") (pin "P$3") (pinfunction "PIN_THREAD_P$3") (pintype "bidirectional"))
      (node (ref "NOT.7") (pin "P$3") (pinfunction "PIN_THREAD_P$3") (pintype "bidirectional"))
      (node (ref "OR2.0") (pin "P$1") (pinfunction "PIN_THREAD_P$1") (pintype "bidirectional"))
      (node (ref "OR2.1") (pin "P$1") (pinfunction "PIN_THREAD_P$1") (pintype "bidirectional"))
      (node (ref "OR2.10") (pin "P$1") (pinfunction "PIN_THREAD_P$1") (pintype "bidirectional"))
      (node (ref "OR2.11") (pin "P$1") (pinfunction "PIN_THREAD_P$1") (pintype "bidirectional"))
      (node (ref "OR2.12") (pin "P$1") (pinfunction "PIN_THREAD_P$1") (pintype "bidirectional"))
      (node (ref "OR2.13") (pin "P$1") (pinfunction "PIN_THREAD_P$1") (pintype "bidirectional"))
      (node (ref "OR2.2") (pin "P$1") (pinfunction "PIN_THREAD_P$1") (pintype "bidirectional"))
      (node (ref "OR2.3") (pin "P$1") (pinfunction "PIN_THREAD_P$1") (pintype "bidirectional"))
      (node (ref "OR2.4") (pin "P$1") (pinfunction "PIN_THREAD_P$1") (pintype "bidirectional"))
      (node (ref "OR2.5") (pin "P$1") (pinfunction "PIN_THREAD_P$1") (pintype "bidirectional"))
      (node (ref "OR2.6") (pin "P$1") (pinfunction "PIN_THREAD_P$1") (pintype "bidirectional"))
      (node (ref "OR2.7") (pin "P$1") (pinfunction "PIN_THREAD_P$1") (pintype "bidirectional"))
      (node (ref "OR2.8") (pin "P$1") (pinfunction "PIN_THREAD_P$1") (pintype "bidirectional"))
      (node (ref "OR2.9") (pin "P$1") (pinfunction "PIN_THREAD_P$1") (pintype "bidirectional"))
      (node (ref "SCALE.0") (pin "P$1") (pinfunction "PIN_THREAD_P$1") (pintype "bidirectional"))
      (node (ref "SCALE.1") (pin "P$1") (pinfunction "PIN_THREAD_P$1") (pintype "bidirectional"))
      (node (ref "SCALE.2") (pin "P$1") (pinfunction "PIN_THREAD_P$1") (pintype "bidirectional"))
      (node (ref "SCALE.3") (pin "P$1") (pinfunction "PIN_THREAD_P$1") (pintype "bidirectional"))
      (node (ref "SCALE.4") (pin "P$1") (pinfunction "PIN_THREAD_P$1") (pintype "bidirectional"))
      (node (ref "SCALE.5") (pin "P$1") (pinfunction "PIN_THREAD_P$1") (pintype "bidirectional"))
      (node (ref "SCALE.6") (pin "P$1") (pinfunction "PIN_THREAD_P$1") (pintype "bidirectional"))
      (node (ref "SERVO-THREAD") (pin "P$7") (pinfunction "__P$7") (pintype "output"))
      (node (ref "TIMEDELAY.0") (pin "P$6") (pinfunction "PIN_THREAD_P$6") (pintype "bidirectional"))
      (node (ref "TOGGLE.0") (pin "P$1") (pinfunction "PIN_THREAD_P$1") (pintype "bidirectional"))
    )
    (net (code "112") (name "TOOL-CHANGE") (class "Default")
      (node (ref "HAL_MANUALTOOLCHANGE") (pin "P$1") (pinfunction "CHANGE_P$1") (pintype "input"))
      (node (ref "IOCONTROL.0") (pin "P$6") (pinfunction "TOOL-CHANGE_P$6") (pintype "output"))
    )
    (net (code "113") (name "TOOL-CHANGED") (class "Default")
      (node (ref "HAL_MANUALTOOLCHANGE") (pin "P$2") (pinfunction "CHANGED_P$2") (pintype "output"))
      (node (ref "IOCONTROL.0") (pin "P$7") (pinfunction "TOOL-CHANGED_P$7") (pintype "input"))
    )
    (net (code "114") (name "TOOL-NUMBER") (class "Default")
      (node (ref "HAL_MANUALTOOLCHANGE") (pin "P$3") (pinfunction "NUMBER_P$3") (pintype "input"))
      (node (ref "IOCONTROL.0") (pin "P$8") (pinfunction "TOOL-PREP-NUMBER_P$8") (pintype "output"))
    )
    (net (code "115") (name "TOOL-PREPARE-LOOPBACK") (class "Default")
      (node (ref "IOCONTROL.0") (pin "P$10") (pinfunction "TOOL-PREPARED_P$10") (pintype "input"))
      (node (ref "IOCONTROL.0") (pin "P$9") (pinfunction "TOOL-PREPARE_P$9") (pintype "output"))
    )
    (net (code "116") (name "VEL-PER-MINUTE") (class "Default")
      (node (ref "SCALE.0") (pin "P$5") (pinfunction "OUT_P$5") (pintype "output"))
      (node (ref "SCALE.1") (pin "P$3") (pinfunction "IN_P$3") (pintype "input"))
      (node (ref "SCALE.2") (pin "P$3") (pinfunction "IN_P$3") (pintype "input"))
    )
    (net (code "117") (name "VEL-PER-SECOND") (class "Default")
      (node (ref "MUX2.0") (pin "P$4") (pinfunction "OUT_P$4") (pintype "output"))
      (node (ref "SCALE.0") (pin "P$3") (pinfunction "IN_P$3") (pintype "input"))
    )
    (net (code "118") (name "X-AMP-ENABLE") (class "Default")
      (node (ref "AXIS.0") (pin "P$22") (pinfunction "AMP-ENABLE-OUT_P$22") (pintype "output"))
      (node (ref "LOGIC.0") (pin "P$3") (pinfunction "IN-00_P$3") (pintype "input"))
      (node (ref "STEPGEN.0") (pin "P$15") (pinfunction "ENABLE_P$15") (pintype "input"))
    )
    (net (code "119") (name "X-ANALOG") (class "Default")
      (node (ref "HALUI.JOG.0") (pin "P$1") (pinfunction "ANALOG_P$1") (pintype "input"))
      (node (ref "MUX2.1") (pin "P$4") (pinfunction "OUT_P$4") (pintype "output"))
    )
    (net (code "120") (name "X-DIRECTION") (class "Default")
      (node (ref "PARPORT.0") (pin "P$35") (pinfunction "PIN-02-OUT_P$35") (pintype "input"))
      (node (ref "STEPGEN.0") (pin "P$14") (pinfunction "DIR_P$14") (pintype "output"))
    )
    (net (code "121") (name "X-DISABLE") (class "Default")
      (node (ref "AND2.12") (pin "P$2") (pinfunction "IN1_P$2") (pintype "input"))
      (node (ref "NOT.4") (pin "P$2") (pinfunction "OUT_P$2") (pintype "output"))
    )
    (net (code "122") (name "X-ENABLE") (class "Default")
      (node (ref "FLIPFLOP.0") (pin "P$3") (pinfunction "OUT_P$3") (pintype "output"))
      (node (ref "MUX2.1") (pin "P$5") (pinfunction "SEL_P$5") (pintype "input"))
      (node (ref "NOT.4") (pin "P$1") (pinfunction "IN_P$1") (pintype "input"))
    )
    (net (code "123") (name "X-HAT-MINUS") (class "Default")
      (node (ref "AND2.1") (pin "P$1") (pinfunction "IN0_P$1") (pintype "input"))
      (node (ref "INPUT.0") (pin "P$4") (pinfunction "ABS-HAT0X-IS-NEG_P$4") (pintype "output"))
      (node (ref "OR2.4") (pin "P$3") (pinfunction "IN1_P$3") (pintype "input"))
    )
    (net (code "124") (name "X-HAT-PLUS") (class "Default")
      (node (ref "AND2.2") (pin "P$1") (pinfunction "IN0_P$1") (pintype "input"))
      (node (ref "INPUT.0") (pin "P$5") (pinfunction "ABS-HAT0X-IS-POS_P$5") (pintype "output"))
      (node (ref "OR2.4") (pin "P$2") (pinfunction "IN0_P$2") (pintype "input"))
    )
    (net (code "125") (name "X-JOG") (class "Default")
      (node (ref "INPUT.0") (pin "P$31") (pinfunction "ABS-X-POSITION_P$31") (pintype "output"))
      (node (ref "MUX2.1") (pin "P$3") (pinfunction "IN1_P$3") (pintype "input"))
    )
    (net (code "126") (name "X-KNOB-ACTIVE") (class "Default")
      (node (ref "AND2.9") (pin "P$1") (pinfunction "IN0_P$1") (pintype "input"))
      (node (ref "NOT.0") (pin "P$1") (pinfunction "IN_P$1") (pintype "input"))
      (node (ref "OR2.7") (pin "P$4") (pinfunction "OUT_P$4") (pintype "output"))
    )
    (net (code "127") (name "X-KNOB-INACTIVE") (class "Default")
      (node (ref "AND2.10") (pin "P$1") (pinfunction "IN0_P$1") (pintype "input"))
      (node (ref "AND2.11") (pin "P$1") (pinfunction "IN0_P$1") (pintype "input"))
      (node (ref "NOT.0") (pin "P$2") (pinfunction "OUT_P$2") (pintype "output"))
    )
    (net (code "128") (name "X-SET") (class "Default")
      (node (ref "AND2.9") (pin "P$3") (pinfunction "OUT_P$3") (pintype "output"))
      (node (ref "FLIPFLOP.0") (pin "P$5") (pinfunction "SET_P$5") (pintype "input"))
    )
    (net (code "129") (name "X-STEP") (class "Default")
      (node (ref "PARPORT.0") (pin "P$36") (pinfunction "PIN-03-OUT_P$36") (pintype "input"))
      (node (ref "STEPGEN.0") (pin "P$18") (pinfunction "STEP_P$18") (pintype "output"))
    )
    (net (code "130") (name "XY-BUTTONS-ACTIVE") (class "Default")
      (node (ref "OR2.12") (pin "P$2") (pinfunction "IN0_P$2") (pintype "input"))
      (node (ref "OR2.13") (pin "P$3") (pinfunction "IN1_P$3") (pintype "input"))
      (node (ref "OR2.5") (pin "P$4") (pinfunction "OUT_P$4") (pintype "output"))
    )
    (net (code "131") (name "XY-RESET") (class "Default")
      (node (ref "AND2.10") (pin "P$3") (pinfunction "OUT_P$3") (pintype "output"))
      (node (ref "FLIPFLOP.0") (pin "P$4") (pinfunction "RESET_P$4") (pintype "input"))
      (node (ref "FLIPFLOP.1") (pin "P$4") (pinfunction "RESET_P$4") (pintype "input"))
    )
    (net (code "132") (name "XYZA-BUTTONS-ACTIVE") (class "Default")
      (node (ref "OR2.13") (pin "P$4") (pinfunction "OUT_P$4") (pintype "output"))
      (node (ref "TIMEDELAY.0") (pin "P$2") (pinfunction "IN_P$2") (pintype "input"))
    )
    (net (code "133") (name "Y-AMP-ENABLE") (class "Default")
      (node (ref "AXIS.1") (pin "P$22") (pinfunction "AMP-ENABLE-OUT_P$22") (pintype "output"))
      (node (ref "LOGIC.0") (pin "P$4") (pinfunction "IN-01_P$4") (pintype "input"))
      (node (ref "STEPGEN.1") (pin "P$15") (pinfunction "ENABLE_P$15") (pintype "input"))
    )
    (net (code "134") (name "Y-ANALOG") (class "Default")
      (node (ref "HALUI.JOG.1") (pin "P$1") (pinfunction "ANALOG_P$1") (pintype "input"))
      (node (ref "MUX2.2") (pin "P$4") (pinfunction "OUT_P$4") (pintype "output"))
    )
    (net (code "135") (name "Y-DIRECTION") (class "Default")
      (node (ref "PARPORT.0") (pin "P$37") (pinfunction "PIN-04-OUT_P$37") (pintype "input"))
      (node (ref "STEPGEN.1") (pin "P$14") (pinfunction "DIR_P$14") (pintype "output"))
    )
    (net (code "136") (name "Y-DISABLE") (class "Default")
      (node (ref "AND2.9") (pin "P$2") (pinfunction "IN1_P$2") (pintype "input"))
      (node (ref "NOT.5") (pin "P$2") (pinfunction "OUT_P$2") (pintype "output"))
    )
    (net (code "137") (name "Y-ENABLE") (class "Default")
      (node (ref "FLIPFLOP.1") (pin "P$3") (pinfunction "OUT_P$3") (pintype "output"))
      (node (ref "MUX2.2") (pin "P$5") (pinfunction "SEL_P$5") (pintype "input"))
      (node (ref "NOT.5") (pin "P$1") (pinfunction "IN_P$1") (pintype "input"))
    )
    (net (code "138") (name "Y-HAT-MINUS") (class "Default")
      (node (ref "AND2.4") (pin "P$1") (pinfunction "IN0_P$1") (pintype "input"))
      (node (ref "INPUT.0") (pin "P$16") (pinfunction "ABS-HAT0Y-IS-NEG_P$16") (pintype "output"))
      (node (ref "OR2.6") (pin "P$3") (pinfunction "IN1_P$3") (pintype "input"))
    )
    (net (code "139") (name "Y-HAT-PLUS") (class "Default")
      (node (ref "AND2.3") (pin "P$1") (pinfunction "IN0_P$1") (pintype "input"))
      (node (ref "INPUT.0") (pin "P$12") (pinfunction "ABS-HAT0Y-IS-POS_P$12") (pintype "output"))
      (node (ref "OR2.6") (pin "P$2") (pinfunction "IN0_P$2") (pintype "input"))
    )
    (net (code "140") (name "Y-JOG") (class "Default")
      (node (ref "INPUT.0") (pin "P$39") (pinfunction "ABS-Y-POSITION_P$39") (pintype "output"))
      (node (ref "SCALE.5") (pin "P$3") (pinfunction "IN_P$3") (pintype "input"))
    )
    (net (code "141") (name "Y-JOG-REVERSED") (class "Default")
      (node (ref "MUX2.2") (pin "P$3") (pinfunction "IN1_P$3") (pintype "input"))
      (node (ref "SCALE.5") (pin "P$5") (pinfunction "OUT_P$5") (pintype "output"))
    )
    (net (code "142") (name "Y-KNOB-ACTIVE") (class "Default")
      (node (ref "AND2.11") (pin "P$2") (pinfunction "IN1_P$2") (pintype "input"))
      (node (ref "NOT.1") (pin "P$1") (pinfunction "IN_P$1") (pintype "input"))
      (node (ref "OR2.8") (pin "P$4") (pinfunction "OUT_P$4") (pintype "output"))
    )
    (net (code "143") (name "Y-KNOB-INACTIVE") (class "Default")
      (node (ref "AND2.10") (pin "P$2") (pinfunction "IN1_P$2") (pintype "input"))
      (node (ref "NOT.1") (pin "P$2") (pinfunction "OUT_P$2") (pintype "output"))
    )
    (net (code "144") (name "Y-SELECT") (class "Default")
      (node (ref "AND2.11") (pin "P$3") (pinfunction "OUT_P$3") (pintype "output"))
      (node (ref "AND2.12") (pin "P$1") (pinfunction "IN0_P$1") (pintype "input"))
    )
    (net (code "145") (name "Y-SET") (class "Default")
      (node (ref "AND2.12") (pin "P$3") (pinfunction "OUT_P$3") (pintype "output"))
      (node (ref "FLIPFLOP.1") (pin "P$5") (pinfunction "SET_P$5") (pintype "input"))
    )
    (net (code "146") (name "Y-STEP") (class "Default")
      (node (ref "PARPORT.0") (pin "P$38") (pinfunction "PIN-05-OUT_P$38") (pintype "input"))
      (node (ref "STEPGEN.1") (pin "P$18") (pinfunction "STEP_P$18") (pintype "output"))
    )
    (net (code "147") (name "Z-AMP-ENABLE") (class "Default")
      (node (ref "AXIS.2") (pin "P$22") (pinfunction "AMP-ENABLE-OUT_P$22") (pintype "output"))
      (node (ref "LOGIC.0") (pin "P$5") (pinfunction "IN-02_P$5") (pintype "input"))
      (node (ref "STEPGEN.2") (pin "P$15") (pinfunction "ENABLE_P$15") (pintype "input"))
    )
    (net (code "148") (name "Z-ANALOG") (class "Default")
      (node (ref "HALUI.JOG.2") (pin "P$1") (pinfunction "ANALOG_P$1") (pintype "input"))
      (node (ref "MUX2.3") (pin "P$4") (pinfunction "OUT_P$4") (pintype "output"))
    )
    (net (code "149") (name "Z-BUTTON-MINUS") (class "Default")
      (node (ref "AND2.5") (pin "P$1") (pinfunction "IN0_P$1") (pintype "input"))
      (node (ref "INPUT.0") (pin "P$65") (pinfunction "BTN-THUMB_P$65") (pintype "output"))
      (node (ref "OR2.2") (pin "P$2") (pinfunction "IN0_P$2") (pintype "input"))
    )
    (net (code "150") (name "Z-BUTTON-PLUS") (class "Default")
      (node (ref "AND2.6") (pin "P$1") (pinfunction "IN0_P$1") (pintype "input"))
      (node (ref "INPUT.0") (pin "P$69") (pinfunction "BTN-TOP_P$69") (pintype "output"))
      (node (ref "OR2.2") (pin "P$3") (pinfunction "IN1_P$3") (pintype "input"))
    )
    (net (code "151") (name "Z-BUTTONS-ACTIVE") (class "Default")
      (node (ref "OR2.1") (pin "P$3") (pinfunction "IN1_P$3") (pintype "input"))
      (node (ref "OR2.2") (pin "P$4") (pinfunction "OUT_P$4") (pintype "output"))
    )
    (net (code "152") (name "Z-DIRECTION") (class "Default")
      (node (ref "PARPORT.0") (pin "P$39") (pinfunction "PIN-06-OUT_P$39") (pintype "input"))
      (node (ref "STEPGEN.2") (pin "P$14") (pinfunction "DIR_P$14") (pintype "output"))
    )
    (net (code "153") (name "Z-DISABLE") (class "Default")
      (node (ref "AND2.16") (pin "P$2") (pinfunction "IN1_P$2") (pintype "input"))
      (node (ref "NOT.6") (pin "P$2") (pinfunction "OUT_P$2") (pintype "output"))
    )
    (net (code "154") (name "Z-ENABLE") (class "Default")
      (node (ref "FLIPFLOP.2") (pin "P$3") (pinfunction "OUT_P$3") (pintype "output"))
      (node (ref "MUX2.3") (pin "P$5") (pinfunction "SEL_P$5") (pintype "input"))
      (node (ref "NOT.6") (pin "P$1") (pinfunction "IN_P$1") (pintype "input"))
    )
    (net (code "155") (name "Z-JOG") (class "Default")
      (node (ref "INPUT.0") (pin "P$23") (pinfunction "ABS-RZ-POSITION_P$23") (pintype "output"))
      (node (ref "SCALE.6") (pin "P$3") (pinfunction "IN_P$3") (pintype "input"))
    )
    (net (code "156") (name "Z-JOG-REVERSED") (class "Default")
      (node (ref "MUX2.3") (pin "P$3") (pinfunction "IN1_P$3") (pintype "input"))
      (node (ref "SCALE.6") (pin "P$5") (pinfunction "OUT_P$5") (pintype "output"))
    )
    (net (code "157") (name "Z-KNOB-ACTIVE") (class "Default")
      (node (ref "AND2.13") (pin "P$1") (pinfunction "IN0_P$1") (pintype "input"))
      (node (ref "NOT.3") (pin "P$1") (pinfunction "IN_P$1") (pintype "input"))
      (node (ref "OR2.10") (pin "P$4") (pinfunction "OUT_P$4") (pintype "output"))
    )
    (net (code "158") (name "Z-KNOB-INACTIVE") (class "Default")
      (node (ref "AND2.14") (pin "P$1") (pinfunction "IN0_P$1") (pintype "input"))
      (node (ref "AND2.15") (pin "P$1") (pinfunction "IN0_P$1") (pintype "input"))
      (node (ref "NOT.3") (pin "P$2") (pinfunction "OUT_P$2") (pintype "output"))
    )
    (net (code "159") (name "Z-SET") (class "Default")
      (node (ref "AND2.13") (pin "P$3") (pinfunction "OUT_P$3") (pintype "output"))
      (node (ref "FLIPFLOP.2") (pin "P$5") (pinfunction "SET_P$5") (pintype "input"))
    )
    (net (code "160") (name "Z-STEP") (class "Default")
      (node (ref "PARPORT.0") (pin "P$40") (pinfunction "PIN-07-OUT_P$40") (pintype "input"))
      (node (ref "STEPGEN.2") (pin "P$18") (pinfunction "STEP_P$18") (pintype "output"))
    )
    (net (code "161") (name "unconnected-(AXIS.0V-AMP-FAULT-IN-PadP$23)") (class "Default")
      (node (ref "AXIS.0") (pin "P$23") (pinfunction "AMP-FAULT-IN_P$23") (pintype "input"))
    )
    (net (code "162") (name "unconnected-(AXIS.0V-HOMING-PadP$25)") (class "Default")
      (node (ref "AXIS.0") (pin "P$25") (pinfunction "HOMING_P$25") (pintype "output"))
    )
    (net (code "163") (name "unconnected-(AXIS.0V-INDEX-ENABLE-PadP$26)") (class "Default")
      (node (ref "AXIS.0") (pin "P$26") (pinfunction "INDEX-ENABLE_P$26") (pintype "bidirectional"))
    )
    (net (code "164") (name "unconnected-(AXIS.0V-JOG-COUNTS-PadP$27)") (class "Default")
      (node (ref "AXIS.0") (pin "P$27") (pinfunction "JOG-COUNTS_P$27") (pintype "input"))
    )
    (net (code "165") (name "unconnected-(AXIS.0V-JOG-ENABLE-PadP$28)") (class "Default")
      (node (ref "AXIS.0") (pin "P$28") (pinfunction "JOG-ENABLE_P$28") (pintype "input"))
    )
    (net (code "166") (name "unconnected-(AXIS.0V-JOG-SCALE-PadP$29)") (class "Default")
      (node (ref "AXIS.0") (pin "P$29") (pinfunction "JOG-SCALE_P$29") (pintype "input"))
    )
    (net (code "167") (name "unconnected-(AXIS.0V-JOG-VEL-MODE-PadP$30)") (class "Default")
      (node (ref "AXIS.0") (pin "P$30") (pinfunction "JOG-VEL-MODE_P$30") (pintype "input"))
    )
    (net (code "168") (name "unconnected-(AXIS.0V-JOINT-POS-CMD-PadP$31)") (class "Default")
      (node (ref "AXIS.0") (pin "P$31") (pinfunction "JOINT-POS-CMD_P$31") (pintype "output"))
    )
    (net (code "169") (name "unconnected-(AXIS.0V-JOINT-POS-FB-PadP$32)") (class "Default")
      (node (ref "AXIS.0") (pin "P$32") (pinfunction "JOINT-POS-FB_P$32") (pintype "output"))
    )
    (net (code "170") (name "unconnected-(AXIS.0V-NEG-LIM-SW-IN-PadP$35)") (class "Default")
      (node (ref "AXIS.0") (pin "P$35") (pinfunction "NEG-LIM-SW-IN_P$35") (pintype "input"))
    )
    (net (code "171") (name "unconnected-(AXIS.0V-POS-LIM-SW-IN-PadP$36)") (class "Default")
      (node (ref "AXIS.0") (pin "P$36") (pinfunction "POS-LIM-SW-IN_P$36") (pintype "input"))
    )
    (net (code "172") (name "unconnected-(AXIS.1V-AMP-FAULT-IN-PadP$23)") (class "Default")
      (node (ref "AXIS.1") (pin "P$23") (pinfunction "AMP-FAULT-IN_P$23") (pintype "input"))
    )
    (net (code "173") (name "unconnected-(AXIS.1V-HOMING-PadP$25)") (class "Default")
      (node (ref "AXIS.1") (pin "P$25") (pinfunction "HOMING_P$25") (pintype "output"))
    )
    (net (code "174") (name "unconnected-(AXIS.1V-INDEX-ENABLE-PadP$26)") (class "Default")
      (node (ref "AXIS.1") (pin "P$26") (pinfunction "INDEX-ENABLE_P$26") (pintype "bidirectional"))
    )
    (net (code "175") (name "unconnected-(AXIS.1V-JOG-COUNTS-PadP$27)") (class "Default")
      (node (ref "AXIS.1") (pin "P$27") (pinfunction "JOG-COUNTS_P$27") (pintype "input"))
    )
    (net (code "176") (name "unconnected-(AXIS.1V-JOG-ENABLE-PadP$28)") (class "Default")
      (node (ref "AXIS.1") (pin "P$28") (pinfunction "JOG-ENABLE_P$28") (pintype "input"))
    )
    (net (code "177") (name "unconnected-(AXIS.1V-JOG-SCALE-PadP$29)") (class "Default")
      (node (ref "AXIS.1") (pin "P$29") (pinfunction "JOG-SCALE_P$29") (pintype "input"))
    )
    (net (code "178") (name "unconnected-(AXIS.1V-JOG-VEL-MODE-PadP$30)") (class "Default")
      (node (ref "AXIS.1") (pin "P$30") (pinfunction "JOG-VEL-MODE_P$30") (pintype "input"))
    )
    (net (code "179") (name "unconnected-(AXIS.1V-JOINT-POS-CMD-PadP$31)") (class "Default")
      (node (ref "AXIS.1") (pin "P$31") (pinfunction "JOINT-POS-CMD_P$31") (pintype "output"))
    )
    (net (code "180") (name "unconnected-(AXIS.1V-JOINT-POS-FB-PadP$32)") (class "Default")
      (node (ref "AXIS.1") (pin "P$32") (pinfunction "JOINT-POS-FB_P$32") (pintype "output"))
    )
    (net (code "181") (name "unconnected-(AXIS.1V-NEG-LIM-SW-IN-PadP$35)") (class "Default")
      (node (ref "AXIS.1") (pin "P$35") (pinfunction "NEG-LIM-SW-IN_P$35") (pintype "input"))
    )
    (net (code "182") (name "unconnected-(AXIS.1V-POS-LIM-SW-IN-PadP$36)") (class "Default")
      (node (ref "AXIS.1") (pin "P$36") (pinfunction "POS-LIM-SW-IN_P$36") (pintype "input"))
    )
    (net (code "183") (name "unconnected-(AXIS.2V-AMP-FAULT-IN-PadP$23)") (class "Default")
      (node (ref "AXIS.2") (pin "P$23") (pinfunction "AMP-FAULT-IN_P$23") (pintype "input"))
    )
    (net (code "184") (name "unconnected-(AXIS.2V-HOMING-PadP$25)") (class "Default")
      (node (ref "AXIS.2") (pin "P$25") (pinfunction "HOMING_P$25") (pintype "output"))
    )
    (net (code "185") (name "unconnected-(AXIS.2V-INDEX-ENABLE-PadP$26)") (class "Default")
      (node (ref "AXIS.2") (pin "P$26") (pinfunction "INDEX-ENABLE_P$26") (pintype "bidirectional"))
    )
    (net (code "186") (name "unconnected-(AXIS.2V-JOG-COUNTS-PadP$27)") (class "Default")
      (node (ref "AXIS.2") (pin "P$27") (pinfunction "JOG-COUNTS_P$27") (pintype "input"))
    )
    (net (code "187") (name "unconnected-(AXIS.2V-JOG-ENABLE-PadP$28)") (class "Default")
      (node (ref "AXIS.2") (pin "P$28") (pinfunction "JOG-ENABLE_P$28") (pintype "input"))
    )
    (net (code "188") (name "unconnected-(AXIS.2V-JOG-SCALE-PadP$29)") (class "Default")
      (node (ref "AXIS.2") (pin "P$29") (pinfunction "JOG-SCALE_P$29") (pintype "input"))
    )
    (net (code "189") (name "unconnected-(AXIS.2V-JOG-VEL-MODE-PadP$30)") (class "Default")
      (node (ref "AXIS.2") (pin "P$30") (pinfunction "JOG-VEL-MODE_P$30") (pintype "input"))
    )
    (net (code "190") (name "unconnected-(AXIS.2V-JOINT-POS-CMD-PadP$31)") (class "Default")
      (node (ref "AXIS.2") (pin "P$31") (pinfunction "JOINT-POS-CMD_P$31") (pintype "output"))
    )
    (net (code "191") (name "unconnected-(AXIS.2V-JOINT-POS-FB-PadP$32)") (class "Default")
      (node (ref "AXIS.2") (pin "P$32") (pinfunction "JOINT-POS-FB_P$32") (pintype "output"))
    )
    (net (code "192") (name "unconnected-(AXIS.2V-NEG-LIM-SW-IN-PadP$35)") (class "Default")
      (node (ref "AXIS.2") (pin "P$35") (pinfunction "NEG-LIM-SW-IN_P$35") (pintype "input"))
    )
    (net (code "193") (name "unconnected-(AXIS.2V-POS-LIM-SW-IN-PadP$36)") (class "Default")
      (node (ref "AXIS.2") (pin "P$36") (pinfunction "POS-LIM-SW-IN_P$36") (pintype "input"))
    )
    (net (code "194") (name "unconnected-(AXIS.3V-AMP-FAULT-IN-PadP$23)") (class "Default")
      (node (ref "AXIS.3") (pin "P$23") (pinfunction "AMP-FAULT-IN_P$23") (pintype "input"))
    )
    (net (code "195") (name "unconnected-(AXIS.3V-HOMING-PadP$25)") (class "Default")
      (node (ref "AXIS.3") (pin "P$25") (pinfunction "HOMING_P$25") (pintype "output"))
    )
    (net (code "196") (name "unconnected-(AXIS.3V-INDEX-ENABLE-PadP$26)") (class "Default")
      (node (ref "AXIS.3") (pin "P$26") (pinfunction "INDEX-ENABLE_P$26") (pintype "bidirectional"))
    )
    (net (code "197") (name "unconnected-(AXIS.3V-JOG-COUNTS-PadP$27)") (class "Default")
      (node (ref "AXIS.3") (pin "P$27") (pinfunction "JOG-COUNTS_P$27") (pintype "input"))
    )
    (net (code "198") (name "unconnected-(AXIS.3V-JOG-ENABLE-PadP$28)") (class "Default")
      (node (ref "AXIS.3") (pin "P$28") (pinfunction "JOG-ENABLE_P$28") (pintype "input"))
    )
    (net (code "199") (name "unconnected-(AXIS.3V-JOG-SCALE-PadP$29)") (class "Default")
      (node (ref "AXIS.3") (pin "P$29") (pinfunction "JOG-SCALE_P$29") (pintype "input"))
    )
    (net (code "200") (name "unconnected-(AXIS.3V-JOG-VEL-MODE-PadP$30)") (class "Default")
      (node (ref "AXIS.3") (pin "P$30") (pinfunction "JOG-VEL-MODE_P$30") (pintype "input"))
    )
    (net (code "201") (name "unconnected-(AXIS.3V-JOINT-POS-CMD-PadP$31)") (class "Default")
      (node (ref "AXIS.3") (pin "P$31") (pinfunction "JOINT-POS-CMD_P$31") (pintype "output"))
    )
    (net (code "202") (name "unconnected-(AXIS.3V-JOINT-POS-FB-PadP$32)") (class "Default")
      (node (ref "AXIS.3") (pin "P$32") (pinfunction "JOINT-POS-FB_P$32") (pintype "output"))
    )
    (net (code "203") (name "unconnected-(AXIS.3V-NEG-LIM-SW-IN-PadP$35)") (class "Default")
      (node (ref "AXIS.3") (pin "P$35") (pinfunction "NEG-LIM-SW-IN_P$35") (pintype "input"))
    )
    (net (code "204") (name "unconnected-(AXIS.3V-POS-LIM-SW-IN-PadP$36)") (class "Default")
      (node (ref "AXIS.3") (pin "P$36") (pinfunction "POS-LIM-SW-IN_P$36") (pintype "input"))
    )
    (net (code "205") (name "unconnected-(BASE-THREAD--1-PadP$1)") (class "Default")
      (node (ref "BASE-THREAD") (pin "P$1") (pinfunction "-1_P$1") (pintype "output"))
    )
    (net (code "206") (name "unconnected-(BASE-THREAD--2-PadP$2)") (class "Default")
      (node (ref "BASE-THREAD") (pin "P$2") (pinfunction "-2_P$2") (pintype "output"))
    )
    (net (code "207") (name "unconnected-(BASE-THREAD--3-PadP$3)") (class "Default")
      (node (ref "BASE-THREAD") (pin "P$3") (pinfunction "-3_P$3") (pintype "output"))
    )
    (net (code "208") (name "unconnected-(BASE-THREAD-1-PadP$4)") (class "Default")
      (node (ref "BASE-THREAD") (pin "P$4") (pinfunction "1_P$4") (pintype "output"))
    )
    (net (code "209") (name "unconnected-(BASE-THREAD-2-PadP$5)") (class "Default")
      (node (ref "BASE-THREAD") (pin "P$5") (pinfunction "2_P$5") (pintype "output"))
    )
    (net (code "210") (name "unconnected-(BASE-THREAD-3-PadP$6)") (class "Default")
      (node (ref "BASE-THREAD") (pin "P$6") (pinfunction "3_P$6") (pintype "output"))
    )
    (net (code "211") (name "unconnected-(CONV-FLOAT-S32.0C-OUT-OF-RANGE-PadP$5)") (class "Default")
      (node (ref "CONV-FLOAT-S32.0") (pin "P$5") (pinfunction "OUT-OF-RANGE_P$5") (pintype "output"))
    )
    (net (code "212") (name "unconnected-(FLIPFLOP.0B-CLK-PadP$1)") (class "Default")
      (node (ref "FLIPFLOP.0") (pin "P$1") (pinfunction "CLK_P$1") (pintype "input"))
    )
    (net (code "213") (name "unconnected-(FLIPFLOP.0B-DATA-PadP$2)") (class "Default")
      (node (ref "FLIPFLOP.0") (pin "P$2") (pinfunction "DATA_P$2") (pintype "input"))
    )
    (net (code "214") (name "unconnected-(FLIPFLOP.1B-CLK-PadP$1)") (class "Default")
      (node (ref "FLIPFLOP.1") (pin "P$1") (pinfunction "CLK_P$1") (pintype "input"))
    )
    (net (code "215") (name "unconnected-(FLIPFLOP.1B-DATA-PadP$2)") (class "Default")
      (node (ref "FLIPFLOP.1") (pin "P$2") (pinfunction "DATA_P$2") (pintype "input"))
    )
    (net (code "216") (name "unconnected-(FLIPFLOP.2B-CLK-PadP$1)") (class "Default")
      (node (ref "FLIPFLOP.2") (pin "P$1") (pinfunction "CLK_P$1") (pintype "input"))
    )
    (net (code "217") (name "unconnected-(FLIPFLOP.2B-DATA-PadP$2)") (class "Default")
      (node (ref "FLIPFLOP.2") (pin "P$2") (pinfunction "DATA_P$2") (pintype "input"))
    )
    (net (code "218") (name "unconnected-(FLIPFLOP.3B-CLK-PadP$1)") (class "Default")
      (node (ref "FLIPFLOP.3") (pin "P$1") (pinfunction "CLK_P$1") (pintype "input"))
    )
    (net (code "219") (name "unconnected-(FLIPFLOP.3B-DATA-PadP$2)") (class "Default")
      (node (ref "FLIPFLOP.3") (pin "P$2") (pinfunction "DATA_P$2") (pintype "input"))
    )
    (net (code "220") (name "unconnected-(HALUID-MODE.AUTO-PadP$65)") (class "Default")
      (node (ref "HALUI") (pin "P$65") (pinfunction "MODE.AUTO_P$65") (pintype "input"))
    )
    (net (code "221") (name "unconnected-(HALUID-MODE.IS-AUTO-PadP$66)") (class "Default")
      (node (ref "HALUI") (pin "P$66") (pinfunction "MODE.IS-AUTO_P$66") (pintype "output"))
    )
    (net (code "222") (name "unconnected-(HALUID-MODE.IS-JOINT-PadP$67)") (class "Default")
      (node (ref "HALUI") (pin "P$67") (pinfunction "MODE.IS-JOINT_P$67") (pintype "output"))
    )
    (net (code "223") (name "unconnected-(HALUID-MODE.IS-MANUAL-PadP$68)") (class "Default")
      (node (ref "HALUI") (pin "P$68") (pinfunction "MODE.IS-MANUAL_P$68") (pintype "output"))
    )
    (net (code "224") (name "unconnected-(HALUID-MODE.IS-MDI-PadP$69)") (class "Default")
      (node (ref "HALUI") (pin "P$69") (pinfunction "MODE.IS-MDI_P$69") (pintype "output"))
    )
    (net (code "225") (name "unconnected-(HALUID-MODE.IS-TELEOP-PadP$70)") (class "Default")
      (node (ref "HALUI") (pin "P$70") (pinfunction "MODE.IS-TELEOP_P$70") (pintype "output"))
    )
    (net (code "226") (name "unconnected-(HALUID-MODE.JOINT-PadP$71)") (class "Default")
      (node (ref "HALUI") (pin "P$71") (pinfunction "MODE.JOINT_P$71") (pintype "input"))
    )
    (net (code "227") (name "unconnected-(HALUID-MODE.MDI-PadP$73)") (class "Default")
      (node (ref "HALUI") (pin "P$73") (pinfunction "MODE.MDI_P$73") (pintype "input"))
    )
    (net (code "228") (name "unconnected-(HALUID-MODE.TELEOP-PadP$74)") (class "Default")
      (node (ref "HALUI") (pin "P$74") (pinfunction "MODE.TELEOP_P$74") (pintype "input"))
    )
    (net (code "229") (name "unconnected-(HALUIE-PROGRAM.BLOCK-DELETE.IS-ON-PadP$33)") (class "Default")
      (node (ref "HALUI") (pin "P$33") (pinfunction "PROGRAM.BLOCK-DELETE.IS-ON_P$33") (pintype "output"))
    )
    (net (code "230") (name "unconnected-(HALUIE-PROGRAM.BLOCK-DELETE.OFF-PadP$34)") (class "Default")
      (node (ref "HALUI") (pin "P$34") (pinfunction "PROGRAM.BLOCK-DELETE.OFF_P$34") (pintype "input"))
    )
    (net (code "231") (name "unconnected-(HALUIE-PROGRAM.BLOCK-DELETE.ON-PadP$35)") (class "Default")
      (node (ref "HALUI") (pin "P$35") (pinfunction "PROGRAM.BLOCK-DELETE.ON_P$35") (pintype "input"))
    )
    (net (code "232") (name "unconnected-(HALUIE-PROGRAM.IS-IDLE-PadP$36)") (class "Default")
      (node (ref "HALUI") (pin "P$36") (pinfunction "PROGRAM.IS-IDLE_P$36") (pintype "output"))
    )
    (net (code "233") (name "unconnected-(HALUIE-PROGRAM.IS-PAUSED-PadP$37)") (class "Default")
      (node (ref "HALUI") (pin "P$37") (pinfunction "PROGRAM.IS-PAUSED_P$37") (pintype "output"))
    )
    (net (code "234") (name "unconnected-(HALUIE-PROGRAM.IS-RUNNING-PadP$38)") (class "Default")
      (node (ref "HALUI") (pin "P$38") (pinfunction "PROGRAM.IS-RUNNING_P$38") (pintype "output"))
    )
    (net (code "235") (name "unconnected-(HALUIE-PROGRAM.OPTIONAL-STOP.IS-ON-PadP$39)") (class "Default")
      (node (ref "HALUI") (pin "P$39") (pinfunction "PROGRAM.OPTIONAL-STOP.IS-ON_P$39") (pintype "output"))
    )
    (net (code "236") (name "unconnected-(HALUIE-PROGRAM.OPTIONAL-STOP.OFF-PadP$40)") (class "Default")
      (node (ref "HALUI") (pin "P$40") (pinfunction "PROGRAM.OPTIONAL-STOP.OFF_P$40") (pintype "input"))
    )
    (net (code "237") (name "unconnected-(HALUIE-PROGRAM.OPTIONAL-STOP.ON-PadP$41)") (class "Default")
      (node (ref "HALUI") (pin "P$41") (pinfunction "PROGRAM.OPTIONAL-STOP.ON_P$41") (pintype "input"))
    )
    (net (code "238") (name "unconnected-(HALUIE-PROGRAM.PAUSE-PadP$42)") (class "Default")
      (node (ref "HALUI") (pin "P$42") (pinfunction "PROGRAM.PAUSE_P$42") (pintype "input"))
    )
    (net (code "239") (name "unconnected-(HALUIE-PROGRAM.RUN-PadP$44)") (class "Default")
      (node (ref "HALUI") (pin "P$44") (pinfunction "PROGRAM.RUN_P$44") (pintype "input"))
    )
    (net (code "240") (name "unconnected-(HALUIE-PROGRAM.STEP-PadP$45)") (class "Default")
      (node (ref "HALUI") (pin "P$45") (pinfunction "PROGRAM.STEP_P$45") (pintype "input"))
    )
    (net (code "241") (name "unconnected-(HALUIE-PROGRAM.STOP-PadP$46)") (class "Default")
      (node (ref "HALUI") (pin "P$46") (pinfunction "PROGRAM.STOP_P$46") (pintype "input"))
    )
    (net (code "242") (name "unconnected-(HALUIH-ABORT-PadP$1)") (class "Default")
      (node (ref "HALUI") (pin "P$1") (pinfunction "ABORT_P$1") (pintype "input"))
    )
    (net (code "243") (name "unconnected-(HALUIH-ESTOP.IS-ACTIVATED-PadP$3)") (class "Default")
      (node (ref "HALUI") (pin "P$3") (pinfunction "ESTOP.IS-ACTIVATED_P$3") (pintype "output"))
    )
    (net (code "244") (name "unconnected-(HALUIH-MACHINE.IS-ON-PadP$5)") (class "Default")
      (node (ref "HALUI") (pin "P$5") (pinfunction "MACHINE.IS-ON_P$5") (pintype "output"))
    )
    (net (code "245") (name "unconnected-(HALUIH-MACHINE.OFF-PadP$6)") (class "Default")
      (node (ref "HALUI") (pin "P$6") (pinfunction "MACHINE.OFF_P$6") (pintype "input"))
    )
    (net (code "246") (name "unconnected-(HALUIH-MACHINE.ON-PadP$7)") (class "Default")
      (node (ref "HALUI") (pin "P$7") (pinfunction "MACHINE.ON_P$7") (pintype "input"))
    )
    (net (code "247") (name "unconnected-(INPUT.0A-ABS-HAT0X-COUNTS-PadP$1)") (class "Default")
      (node (ref "INPUT.0") (pin "P$1") (pinfunction "ABS-HAT0X-COUNTS_P$1") (pintype "output"))
    )
    (net (code "248") (name "unconnected-(INPUT.0A-ABS-HAT0X-FLAT-PadP$2)") (class "Default")
      (node (ref "INPUT.0") (pin "P$2") (pinfunction "ABS-HAT0X-FLAT_P$2") (pintype "input"))
    )
    (net (code "249") (name "unconnected-(INPUT.0A-ABS-HAT0X-FUZZ-PadP$3)") (class "Default")
      (node (ref "INPUT.0") (pin "P$3") (pinfunction "ABS-HAT0X-FUZZ_P$3") (pintype "input"))
    )
    (net (code "250") (name "unconnected-(INPUT.0A-ABS-HAT0X-OFFSET-PadP$6)") (class "Default")
      (node (ref "INPUT.0") (pin "P$6") (pinfunction "ABS-HAT0X-OFFSET_P$6") (pintype "input"))
    )
    (net (code "251") (name "unconnected-(INPUT.0A-ABS-HAT0X-POSITION-PadP$7)") (class "Default")
      (node (ref "INPUT.0") (pin "P$7") (pinfunction "ABS-HAT0X-POSITION_P$7") (pintype "output"))
    )
    (net (code "252") (name "unconnected-(INPUT.0A-ABS-HAT0X-SCALE-PadP$8)") (class "Default")
      (node (ref "INPUT.0") (pin "P$8") (pinfunction "ABS-HAT0X-SCALE_P$8") (pintype "input"))
    )
    (net (code "253") (name "unconnected-(INPUT.0A-ABS-HAT0Y-COUNTS-PadP$9)") (class "Default")
      (node (ref "INPUT.0") (pin "P$9") (pinfunction "ABS-HAT0Y-COUNTS_P$9") (pintype "output"))
    )
    (net (code "254") (name "unconnected-(INPUT.0A-ABS-HAT0Y-FLAT-PadP$10)") (class "Default")
      (node (ref "INPUT.0") (pin "P$10") (pinfunction "ABS-HAT0Y-FLAT_P$10") (pintype "input"))
    )
    (net (code "255") (name "unconnected-(INPUT.0A-ABS-HAT0Y-FUZZ-PadP$11)") (class "Default")
      (node (ref "INPUT.0") (pin "P$11") (pinfunction "ABS-HAT0Y-FUZZ_P$11") (pintype "input"))
    )
    (net (code "256") (name "unconnected-(INPUT.0A-ABS-HAT0Y-OFFSET-PadP$13)") (class "Default")
      (node (ref "INPUT.0") (pin "P$13") (pinfunction "ABS-HAT0Y-OFFSET_P$13") (pintype "input"))
    )
    (net (code "257") (name "unconnected-(INPUT.0A-ABS-HAT0Y-POSITION-PadP$14)") (class "Default")
      (node (ref "INPUT.0") (pin "P$14") (pinfunction "ABS-HAT0Y-POSITION_P$14") (pintype "output"))
    )
    (net (code "258") (name "unconnected-(INPUT.0A-ABS-HAT0Y-SCALE-PadP$15)") (class "Default")
      (node (ref "INPUT.0") (pin "P$15") (pinfunction "ABS-HAT0Y-SCALE_P$15") (pintype "input"))
    )
    (net (code "259") (name "unconnected-(INPUT.0A-ABS-RZ-COUNTS-PadP$17)") (class "Default")
      (node (ref "INPUT.0") (pin "P$17") (pinfunction "ABS-RZ-COUNTS_P$17") (pintype "output"))
    )
    (net (code "260") (name "unconnected-(INPUT.0A-ABS-RZ-FUZZ-PadP$19)") (class "Default")
      (node (ref "INPUT.0") (pin "P$19") (pinfunction "ABS-RZ-FUZZ_P$19") (pintype "input"))
    )
    (net (code "261") (name "unconnected-(INPUT.0A-ABS-RZ-OFFSET-PadP$22)") (class "Default")
      (node (ref "INPUT.0") (pin "P$22") (pinfunction "ABS-RZ-OFFSET_P$22") (pintype "input"))
    )
    (net (code "262") (name "unconnected-(INPUT.0A-ABS-RZ-SCALE-PadP$24)") (class "Default")
      (node (ref "INPUT.0") (pin "P$24") (pinfunction "ABS-RZ-SCALE_P$24") (pintype "input"))
    )
    (net (code "263") (name "unconnected-(INPUT.0A-ABS-X-COUNTS-PadP$25)") (class "Default")
      (node (ref "INPUT.0") (pin "P$25") (pinfunction "ABS-X-COUNTS_P$25") (pintype "output"))
    )
    (net (code "264") (name "unconnected-(INPUT.0A-ABS-X-FUZZ-PadP$27)") (class "Default")
      (node (ref "INPUT.0") (pin "P$27") (pinfunction "ABS-X-FUZZ_P$27") (pintype "input"))
    )
    (net (code "265") (name "unconnected-(INPUT.0A-ABS-X-OFFSET-PadP$30)") (class "Default")
      (node (ref "INPUT.0") (pin "P$30") (pinfunction "ABS-X-OFFSET_P$30") (pintype "input"))
    )
    (net (code "266") (name "unconnected-(INPUT.0A-ABS-X-SCALE-PadP$32)") (class "Default")
      (node (ref "INPUT.0") (pin "P$32") (pinfunction "ABS-X-SCALE_P$32") (pintype "input"))
    )
    (net (code "267") (name "unconnected-(INPUT.0A-ABS-Y-COUNTS-PadP$33)") (class "Default")
      (node (ref "INPUT.0") (pin "P$33") (pinfunction "ABS-Y-COUNTS_P$33") (pintype "output"))
    )
    (net (code "268") (name "unconnected-(INPUT.0A-ABS-Y-FUZZ-PadP$35)") (class "Default")
      (node (ref "INPUT.0") (pin "P$35") (pinfunction "ABS-Y-FUZZ_P$35") (pintype "input"))
    )
    (net (code "269") (name "unconnected-(INPUT.0A-ABS-Y-OFFSET-PadP$38)") (class "Default")
      (node (ref "INPUT.0") (pin "P$38") (pinfunction "ABS-Y-OFFSET_P$38") (pintype "input"))
    )
    (net (code "270") (name "unconnected-(INPUT.0A-ABS-Y-SCALE-PadP$40)") (class "Default")
      (node (ref "INPUT.0") (pin "P$40") (pinfunction "ABS-Y-SCALE_P$40") (pintype "input"))
    )
    (net (code "271") (name "unconnected-(INPUT.0A-ABS-Z-COUNTS-PadP$41)") (class "Default")
      (node (ref "INPUT.0") (pin "P$41") (pinfunction "ABS-Z-COUNTS_P$41") (pintype "output"))
    )
    (net (code "272") (name "unconnected-(INPUT.0A-ABS-Z-FUZZ-PadP$43)") (class "Default")
      (node (ref "INPUT.0") (pin "P$43") (pinfunction "ABS-Z-FUZZ_P$43") (pintype "input"))
    )
    (net (code "273") (name "unconnected-(INPUT.0A-ABS-Z-OFFSET-PadP$46)") (class "Default")
      (node (ref "INPUT.0") (pin "P$46") (pinfunction "ABS-Z-OFFSET_P$46") (pintype "input"))
    )
    (net (code "274") (name "unconnected-(INPUT.0A-ABS-Z-SCALE-PadP$48)") (class "Default")
      (node (ref "INPUT.0") (pin "P$48") (pinfunction "ABS-Z-SCALE_P$48") (pintype "input"))
    )
    (net (code "275") (name "unconnected-(INPUT.0B-BTN-BASE-NOT-PadP$50)") (class "Default")
      (node (ref "INPUT.0") (pin "P$50") (pinfunction "BTN-BASE-NOT_P$50") (pintype "output"))
    )
    (net (code "276") (name "unconnected-(INPUT.0B-BTN-BASE2-NOT-PadP$52)") (class "Default")
      (node (ref "INPUT.0") (pin "P$52") (pinfunction "BTN-BASE2-NOT_P$52") (pintype "output"))
    )
    (net (code "277") (name "unconnected-(INPUT.0B-BTN-BASE3-NOT-PadP$54)") (class "Default")
      (node (ref "INPUT.0") (pin "P$54") (pinfunction "BTN-BASE3-NOT_P$54") (pintype "output"))
    )
    (net (code "278") (name "unconnected-(INPUT.0B-BTN-BASE4-NOT-PadP$56)") (class "Default")
      (node (ref "INPUT.0") (pin "P$56") (pinfunction "BTN-BASE4-NOT_P$56") (pintype "output"))
    )
    (net (code "279") (name "unconnected-(INPUT.0B-BTN-BASE5-NOT-PadP$58)") (class "Default")
      (node (ref "INPUT.0") (pin "P$58") (pinfunction "BTN-BASE5-NOT_P$58") (pintype "output"))
    )
    (net (code "280") (name "unconnected-(INPUT.0B-BTN-BASE6-NOT-PadP$60)") (class "Default")
      (node (ref "INPUT.0") (pin "P$60") (pinfunction "BTN-BASE6-NOT_P$60") (pintype "output"))
    )
    (net (code "281") (name "unconnected-(INPUT.0B-BTN-JOYSTICK-NOT-PadP$62)") (class "Default")
      (node (ref "INPUT.0") (pin "P$62") (pinfunction "BTN-JOYSTICK-NOT_P$62") (pintype "output"))
    )
    (net (code "282") (name "unconnected-(INPUT.0B-BTN-PINKIE-NOT-PadP$64)") (class "Default")
      (node (ref "INPUT.0") (pin "P$64") (pinfunction "BTN-PINKIE-NOT_P$64") (pintype "output"))
    )
    (net (code "283") (name "unconnected-(INPUT.0B-BTN-PINKIE-PadP$63)") (class "Default")
      (node (ref "INPUT.0") (pin "P$63") (pinfunction "BTN-PINKIE_P$63") (pintype "output"))
    )
    (net (code "284") (name "unconnected-(INPUT.0B-BTN-THUMB-NOT-PadP$66)") (class "Default")
      (node (ref "INPUT.0") (pin "P$66") (pinfunction "BTN-THUMB-NOT_P$66") (pintype "output"))
    )
    (net (code "285") (name "unconnected-(INPUT.0B-BTN-THUMB2-NOT-PadP$68)") (class "Default")
      (node (ref "INPUT.0") (pin "P$68") (pinfunction "BTN-THUMB2-NOT_P$68") (pintype "output"))
    )
    (net (code "286") (name "unconnected-(INPUT.0B-BTN-TOP-NOT-PadP$70)") (class "Default")
      (node (ref "INPUT.0") (pin "P$70") (pinfunction "BTN-TOP-NOT_P$70") (pintype "output"))
    )
    (net (code "287") (name "unconnected-(INPUT.0B-BTN-TOP2-NOT-PadP$72)") (class "Default")
      (node (ref "INPUT.0") (pin "P$72") (pinfunction "BTN-TOP2-NOT_P$72") (pintype "output"))
    )
    (net (code "288") (name "unconnected-(IOCONTROL.0-COOLANT-FLOOD-PadP$1)") (class "Default")
      (node (ref "IOCONTROL.0") (pin "P$1") (pinfunction "COOLANT-FLOOD_P$1") (pintype "output"))
    )
    (net (code "289") (name "unconnected-(IOCONTROL.0-COOLANT-MIST-PadP$2)") (class "Default")
      (node (ref "IOCONTROL.0") (pin "P$2") (pinfunction "COOLANT-MIST_P$2") (pintype "output"))
    )
    (net (code "290") (name "unconnected-(IOCONTROL.0-LUBE-PadP$4)") (class "Default")
      (node (ref "IOCONTROL.0") (pin "P$4") (pinfunction "LUBE_P$4") (pintype "output"))
    )
    (net (code "291") (name "unconnected-(IOCONTROL.0-LUBE_LEVEL-PadP$5)") (class "Default")
      (node (ref "IOCONTROL.0") (pin "P$5") (pinfunction "LUBE_LEVEL_P$5") (pintype "input"))
    )
    (net (code "292") (name "unconnected-(IOCONTROL.0-TOOL-NUMBER-PadP$13)") (class "Default")
      (node (ref "IOCONTROL.0") (pin "P$13") (pinfunction "TOOL-NUMBER_P$13") (pintype "output"))
    )
    (net (code "293") (name "unconnected-(IOCONTROL.0-TOOL-PREP-POCKET-PadP$14)") (class "Default")
      (node (ref "IOCONTROL.0") (pin "P$14") (pinfunction "TOOL-PREP-POCKET_P$14") (pintype "output"))
    )
    (net (code "294") (name "unconnected-(IOCONTROL.0-USER-REQUEST-ENABLE-PadP$12)") (class "Default")
      (node (ref "IOCONTROL.0") (pin "P$12") (pinfunction "USER-REQUEST-ENABLE_P$12") (pintype "output"))
    )
    (net (code "295") (name "unconnected-(LOGIC.0B-IN-04-PadP$7)") (class "Default")
      (node (ref "LOGIC.0") (pin "P$7") (pinfunction "IN-04_P$7") (pintype "input"))
    )
    (net (code "296") (name "unconnected-(LOGIC.0B-IN-05-PadP$8)") (class "Default")
      (node (ref "LOGIC.0") (pin "P$8") (pinfunction "IN-05_P$8") (pintype "input"))
    )
    (net (code "297") (name "unconnected-(LOGIC.0B-IN-06-PadP$9)") (class "Default")
      (node (ref "LOGIC.0") (pin "P$9") (pinfunction "IN-06_P$9") (pintype "input"))
    )
    (net (code "298") (name "unconnected-(LOGIC.0B-IN-07-PadP$10)") (class "Default")
      (node (ref "LOGIC.0") (pin "P$10") (pinfunction "IN-07_P$10") (pintype "input"))
    )
    (net (code "299") (name "unconnected-(LOGIC.0B-IN-08-PadP$11)") (class "Default")
      (node (ref "LOGIC.0") (pin "P$11") (pinfunction "IN-08_P$11") (pintype "input"))
    )
    (net (code "300") (name "unconnected-(LOGIC.0B-IN-09-PadP$12)") (class "Default")
      (node (ref "LOGIC.0") (pin "P$12") (pinfunction "IN-09_P$12") (pintype "input"))
    )
    (net (code "301") (name "unconnected-(LOGIC.0B-IN-10-PadP$13)") (class "Default")
      (node (ref "LOGIC.0") (pin "P$13") (pinfunction "IN-10_P$13") (pintype "input"))
    )
    (net (code "302") (name "unconnected-(LOGIC.0B-IN-11-PadP$14)") (class "Default")
      (node (ref "LOGIC.0") (pin "P$14") (pinfunction "IN-11_P$14") (pintype "input"))
    )
    (net (code "303") (name "unconnected-(LOGIC.0B-IN-12-PadP$15)") (class "Default")
      (node (ref "LOGIC.0") (pin "P$15") (pinfunction "IN-12_P$15") (pintype "input"))
    )
    (net (code "304") (name "unconnected-(LOGIC.0B-IN-13-PadP$16)") (class "Default")
      (node (ref "LOGIC.0") (pin "P$16") (pinfunction "IN-13_P$16") (pintype "input"))
    )
    (net (code "305") (name "unconnected-(LOGIC.0B-IN-14-PadP$17)") (class "Default")
      (node (ref "LOGIC.0") (pin "P$17") (pinfunction "IN-14_P$17") (pintype "input"))
    )
    (net (code "306") (name "unconnected-(LOGIC.0B-IN-15-PadP$18)") (class "Default")
      (node (ref "LOGIC.0") (pin "P$18") (pinfunction "IN-15_P$18") (pintype "input"))
    )
    (net (code "307") (name "unconnected-(LOGIC.0B-OR-PadP$19)") (class "Default")
      (node (ref "LOGIC.0") (pin "P$19") (pinfunction "OR_P$19") (pintype "output"))
    )
    (net (code "308") (name "unconnected-(LOGIC.0B-XOR-PadP$20)") (class "Default")
      (node (ref "LOGIC.0") (pin "P$20") (pinfunction "XOR_P$20") (pintype "output"))
    )
    (net (code "309") (name "unconnected-(MOTIONK-ADAPTIVE-FEED-PadP$11)") (class "Default")
      (node (ref "MOTION") (pin "P$11") (pinfunction "ADAPTIVE-FEED_P$11") (pintype "input"))
    )
    (net (code "310") (name "unconnected-(MOTIONK-DIGITAL-IN-00-PadP$12)") (class "Default")
      (node (ref "MOTION") (pin "P$12") (pinfunction "DIGITAL-IN-00_P$12") (pintype "input"))
    )
    (net (code "311") (name "unconnected-(MOTIONK-DIGITAL-IN-01-PadP$13)") (class "Default")
      (node (ref "MOTION") (pin "P$13") (pinfunction "DIGITAL-IN-01_P$13") (pintype "input"))
    )
    (net (code "312") (name "unconnected-(MOTIONK-DIGITAL-IN-02-PadP$14)") (class "Default")
      (node (ref "MOTION") (pin "P$14") (pinfunction "DIGITAL-IN-02_P$14") (pintype "input"))
    )
    (net (code "313") (name "unconnected-(MOTIONK-DIGITAL-IN-03-PadP$15)") (class "Default")
      (node (ref "MOTION") (pin "P$15") (pinfunction "DIGITAL-IN-03_P$15") (pintype "input"))
    )
    (net (code "314") (name "unconnected-(MOTIONK-DIGITAL-OUT-00-PadP$16)") (class "Default")
      (node (ref "MOTION") (pin "P$16") (pinfunction "DIGITAL-OUT-00_P$16") (pintype "output"))
    )
    (net (code "315") (name "unconnected-(MOTIONK-DIGITAL-OUT-01-PadP$17)") (class "Default")
      (node (ref "MOTION") (pin "P$17") (pinfunction "DIGITAL-OUT-01_P$17") (pintype "output"))
    )
    (net (code "316") (name "unconnected-(MOTIONK-DIGITAL-OUT-02-PadP$18)") (class "Default")
      (node (ref "MOTION") (pin "P$18") (pinfunction "DIGITAL-OUT-02_P$18") (pintype "output"))
    )
    (net (code "317") (name "unconnected-(MOTIONK-DIGITAL-OUT-03-PadP$19)") (class "Default")
      (node (ref "MOTION") (pin "P$19") (pinfunction "DIGITAL-OUT-03_P$19") (pintype "output"))
    )
    (net (code "318") (name "unconnected-(MOTIONK-ENABLE-PadP$20)") (class "Default")
      (node (ref "MOTION") (pin "P$20") (pinfunction "ENABLE_P$20") (pintype "input"))
    )
    (net (code "319") (name "unconnected-(MOTIONK-FEED-HOLD-PadP$21)") (class "Default")
      (node (ref "MOTION") (pin "P$21") (pinfunction "FEED-HOLD_P$21") (pintype "input"))
    )
    (net (code "320") (name "unconnected-(MOTIONK-MOTION-INPOS-PadP$22)") (class "Default")
      (node (ref "MOTION") (pin "P$22") (pinfunction "MOTION-INPOS_P$22") (pintype "output"))
    )
    (net (code "321") (name "unconnected-(MOTIONK-SPINDLE-BRAKE-PadP$24)") (class "Default")
      (node (ref "MOTION") (pin "P$24") (pinfunction "SPINDLE-BRAKE_P$24") (pintype "output"))
    )
    (net (code "322") (name "unconnected-(MOTIONK-SPINDLE-FORWARD-PadP$25)") (class "Default")
      (node (ref "MOTION") (pin "P$25") (pinfunction "SPINDLE-FORWARD_P$25") (pintype "output"))
    )
    (net (code "323") (name "unconnected-(MOTIONK-SPINDLE-INDEX-ENABLE-PadP$26)") (class "Default")
      (node (ref "MOTION") (pin "P$26") (pinfunction "SPINDLE-INDEX-ENABLE_P$26") (pintype "bidirectional"))
    )
    (net (code "324") (name "unconnected-(MOTIONK-SPINDLE-ON-PadP$27)") (class "Default")
      (node (ref "MOTION") (pin "P$27") (pinfunction "SPINDLE-ON_P$27") (pintype "output"))
    )
    (net (code "325") (name "unconnected-(MOTIONK-SPINDLE-REVERSE-PadP$28)") (class "Default")
      (node (ref "MOTION") (pin "P$28") (pinfunction "SPINDLE-REVERSE_P$28") (pintype "output"))
    )
    (net (code "326") (name "unconnected-(MOTIONK-SPINDLE-REVS-PadP$29)") (class "Default")
      (node (ref "MOTION") (pin "P$29") (pinfunction "SPINDLE-REVS_P$29") (pintype "input"))
    )
    (net (code "327") (name "unconnected-(MOTIONK-SPINDLE-SPEED-IN-PadP$30)") (class "Default")
      (node (ref "MOTION") (pin "P$30") (pinfunction "SPINDLE-SPEED-IN_P$30") (pintype "input"))
    )
    (net (code "328") (name "unconnected-(MOTIONK-SPINDLE-SPEED-OUT-PadP$31)") (class "Default")
      (node (ref "MOTION") (pin "P$31") (pinfunction "SPINDLE-SPEED-OUT_P$31") (pintype "output"))
    )
    (net (code "329") (name "unconnected-(PARPORT.0A-PIN-10-IN-PadP$24)") (class "Default")
      (node (ref "PARPORT.0") (pin "P$24") (pinfunction "PIN-10-IN_P$24") (pintype "output"))
    )
    (net (code "330") (name "unconnected-(PARPORT.0A-PIN-11-IN-NOT-PadP$27)") (class "Default")
      (node (ref "PARPORT.0") (pin "P$27") (pinfunction "PIN-11-IN-NOT_P$27") (pintype "output"))
    )
    (net (code "331") (name "unconnected-(PARPORT.0A-PIN-11-IN-PadP$26)") (class "Default")
      (node (ref "PARPORT.0") (pin "P$26") (pinfunction "PIN-11-IN_P$26") (pintype "output"))
    )
    (net (code "332") (name "unconnected-(PARPORT.0A-PIN-12-IN-NOT-PadP$29)") (class "Default")
      (node (ref "PARPORT.0") (pin "P$29") (pinfunction "PIN-12-IN-NOT_P$29") (pintype "output"))
    )
    (net (code "333") (name "unconnected-(PARPORT.0A-PIN-12-IN-PadP$28)") (class "Default")
      (node (ref "PARPORT.0") (pin "P$28") (pinfunction "PIN-12-IN_P$28") (pintype "output"))
    )
    (net (code "334") (name "unconnected-(PARPORT.0A-PIN-13-IN-NOT-PadP$31)") (class "Default")
      (node (ref "PARPORT.0") (pin "P$31") (pinfunction "PIN-13-IN-NOT_P$31") (pintype "output"))
    )
    (net (code "335") (name "unconnected-(PARPORT.0A-PIN-13-IN-PadP$30)") (class "Default")
      (node (ref "PARPORT.0") (pin "P$30") (pinfunction "PIN-13-IN_P$30") (pintype "output"))
    )
    (net (code "336") (name "unconnected-(PARPORT.0A-PIN-15-IN-PadP$32)") (class "Default")
      (node (ref "PARPORT.0") (pin "P$32") (pinfunction "PIN-15-IN_P$32") (pintype "output"))
    )
    (net (code "337") (name "unconnected-(PARPORT.0B-PIN-14-OUT-PadP$43)") (class "Default")
      (node (ref "PARPORT.0") (pin "P$43") (pinfunction "PIN-14-OUT_P$43") (pintype "input"))
    )
    (net (code "338") (name "unconnected-(PARPORT.0B-PIN-16-OUT-PadP$44)") (class "Default")
      (node (ref "PARPORT.0") (pin "P$44") (pinfunction "PIN-16-OUT_P$44") (pintype "input"))
    )
    (net (code "339") (name "unconnected-(SCALE.0B-OFFSET-PadP$4)") (class "Default")
      (node (ref "SCALE.0") (pin "P$4") (pinfunction "OFFSET_P$4") (pintype "input"))
    )
    (net (code "340") (name "unconnected-(SCALE.1B-OFFSET-PadP$4)") (class "Default")
      (node (ref "SCALE.1") (pin "P$4") (pinfunction "OFFSET_P$4") (pintype "input"))
    )
    (net (code "341") (name "unconnected-(SCALE.2B-OFFSET-PadP$4)") (class "Default")
      (node (ref "SCALE.2") (pin "P$4") (pinfunction "OFFSET_P$4") (pintype "input"))
    )
    (net (code "342") (name "unconnected-(SCALE.3B-OFFSET-PadP$4)") (class "Default")
      (node (ref "SCALE.3") (pin "P$4") (pinfunction "OFFSET_P$4") (pintype "input"))
    )
    (net (code "343") (name "unconnected-(SCALE.4B-OFFSET-PadP$4)") (class "Default")
      (node (ref "SCALE.4") (pin "P$4") (pinfunction "OFFSET_P$4") (pintype "input"))
    )
    (net (code "344") (name "unconnected-(SCALE.5B-OFFSET-PadP$4)") (class "Default")
      (node (ref "SCALE.5") (pin "P$4") (pinfunction "OFFSET_P$4") (pintype "input"))
    )
    (net (code "345") (name "unconnected-(SCALE.6B-OFFSET-PadP$4)") (class "Default")
      (node (ref "SCALE.6") (pin "P$4") (pinfunction "OFFSET_P$4") (pintype "input"))
    )
    (net (code "346") (name "unconnected-(SERVO-THREAD--1-PadP$1)") (class "Default")
      (node (ref "SERVO-THREAD") (pin "P$1") (pinfunction "-1_P$1") (pintype "output"))
    )
    (net (code "347") (name "unconnected-(SERVO-THREAD--2-PadP$2)") (class "Default")
      (node (ref "SERVO-THREAD") (pin "P$2") (pinfunction "-2_P$2") (pintype "output"))
    )
    (net (code "348") (name "unconnected-(SERVO-THREAD--3-PadP$3)") (class "Default")
      (node (ref "SERVO-THREAD") (pin "P$3") (pinfunction "-3_P$3") (pintype "output"))
    )
    (net (code "349") (name "unconnected-(SERVO-THREAD-1-PadP$4)") (class "Default")
      (node (ref "SERVO-THREAD") (pin "P$4") (pinfunction "1_P$4") (pintype "output"))
    )
    (net (code "350") (name "unconnected-(SERVO-THREAD-2-PadP$5)") (class "Default")
      (node (ref "SERVO-THREAD") (pin "P$5") (pinfunction "2_P$5") (pintype "output"))
    )
    (net (code "351") (name "unconnected-(SERVO-THREAD-3-PadP$6)") (class "Default")
      (node (ref "SERVO-THREAD") (pin "P$6") (pinfunction "3_P$6") (pintype "output"))
    )
    (net (code "352") (name "unconnected-(STEPGEN.0J-COUNTS-PadP$13)") (class "Default")
      (node (ref "STEPGEN.0") (pin "P$13") (pinfunction "COUNTS_P$13") (pintype "output"))
    )
    (net (code "353") (name "unconnected-(STEPGEN.1J-COUNTS-PadP$13)") (class "Default")
      (node (ref "STEPGEN.1") (pin "P$13") (pinfunction "COUNTS_P$13") (pintype "output"))
    )
    (net (code "354") (name "unconnected-(STEPGEN.2J-COUNTS-PadP$13)") (class "Default")
      (node (ref "STEPGEN.2") (pin "P$13") (pinfunction "COUNTS_P$13") (pintype "output"))
    )
    (net (code "355") (name "unconnected-(STEPGEN.3J-COUNTS-PadP$13)") (class "Default")
      (node (ref "STEPGEN.3") (pin "P$13") (pinfunction "COUNTS_P$13") (pintype "output"))
    )
    (net (code "356") (name "unconnected-(TIMEDELAY.0B-ELAPSED-PadP$1)") (class "Default")
      (node (ref "TIMEDELAY.0") (pin "P$1") (pinfunction "ELAPSED_P$1") (pintype "output"))
    )
  )
)
